# sha2017_rev1_0_0.net
KiCad netlist of a schematic drawn in EAGLE
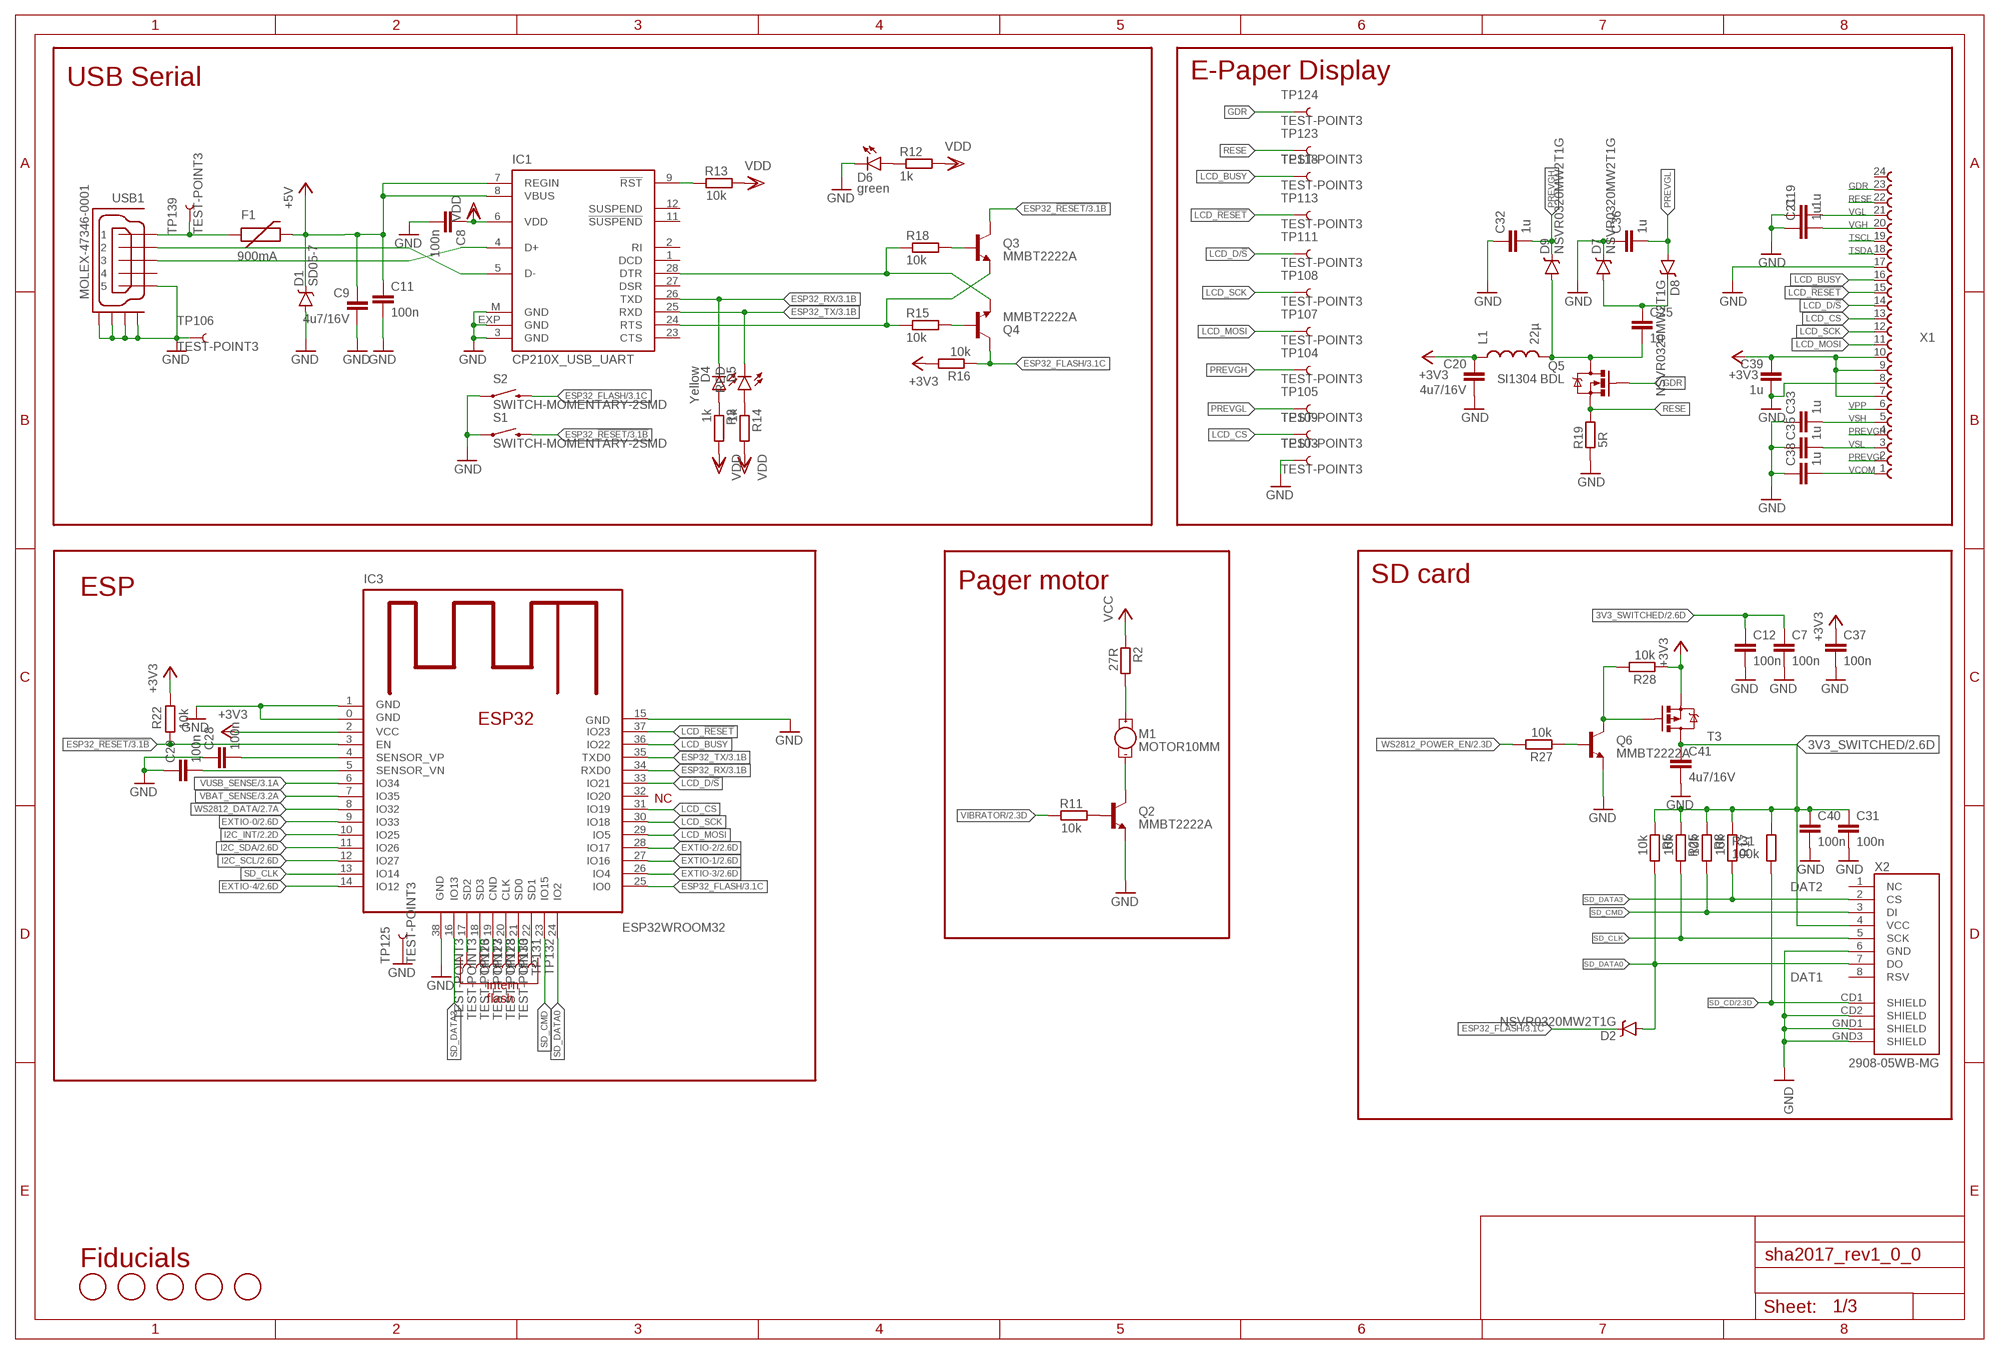
[diagram p0: schematic, sheet 1]
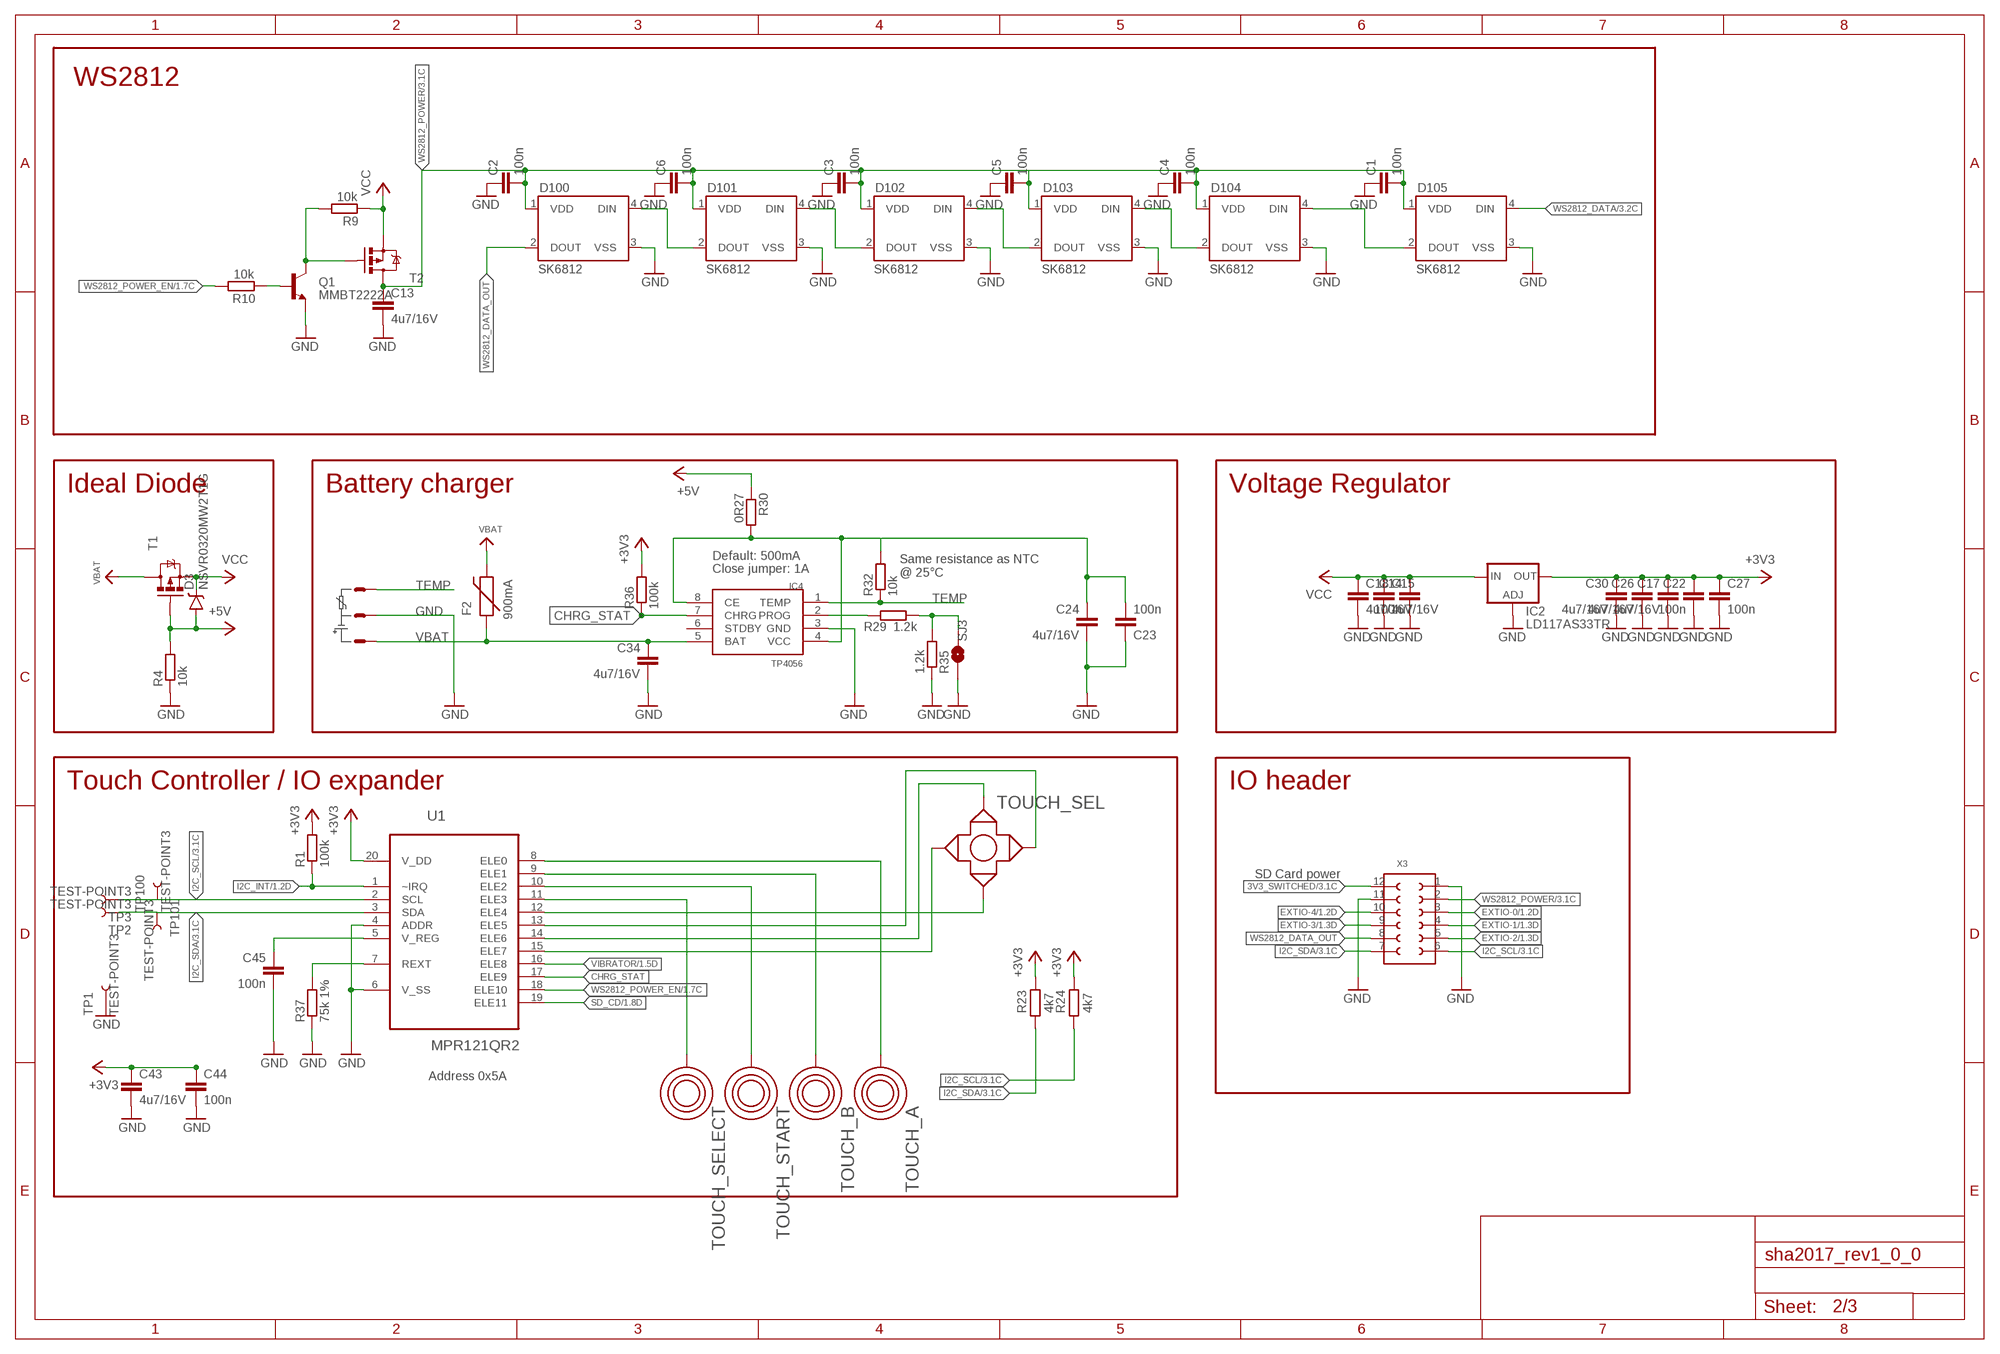
[diagram p1: schematic, sheet 2]
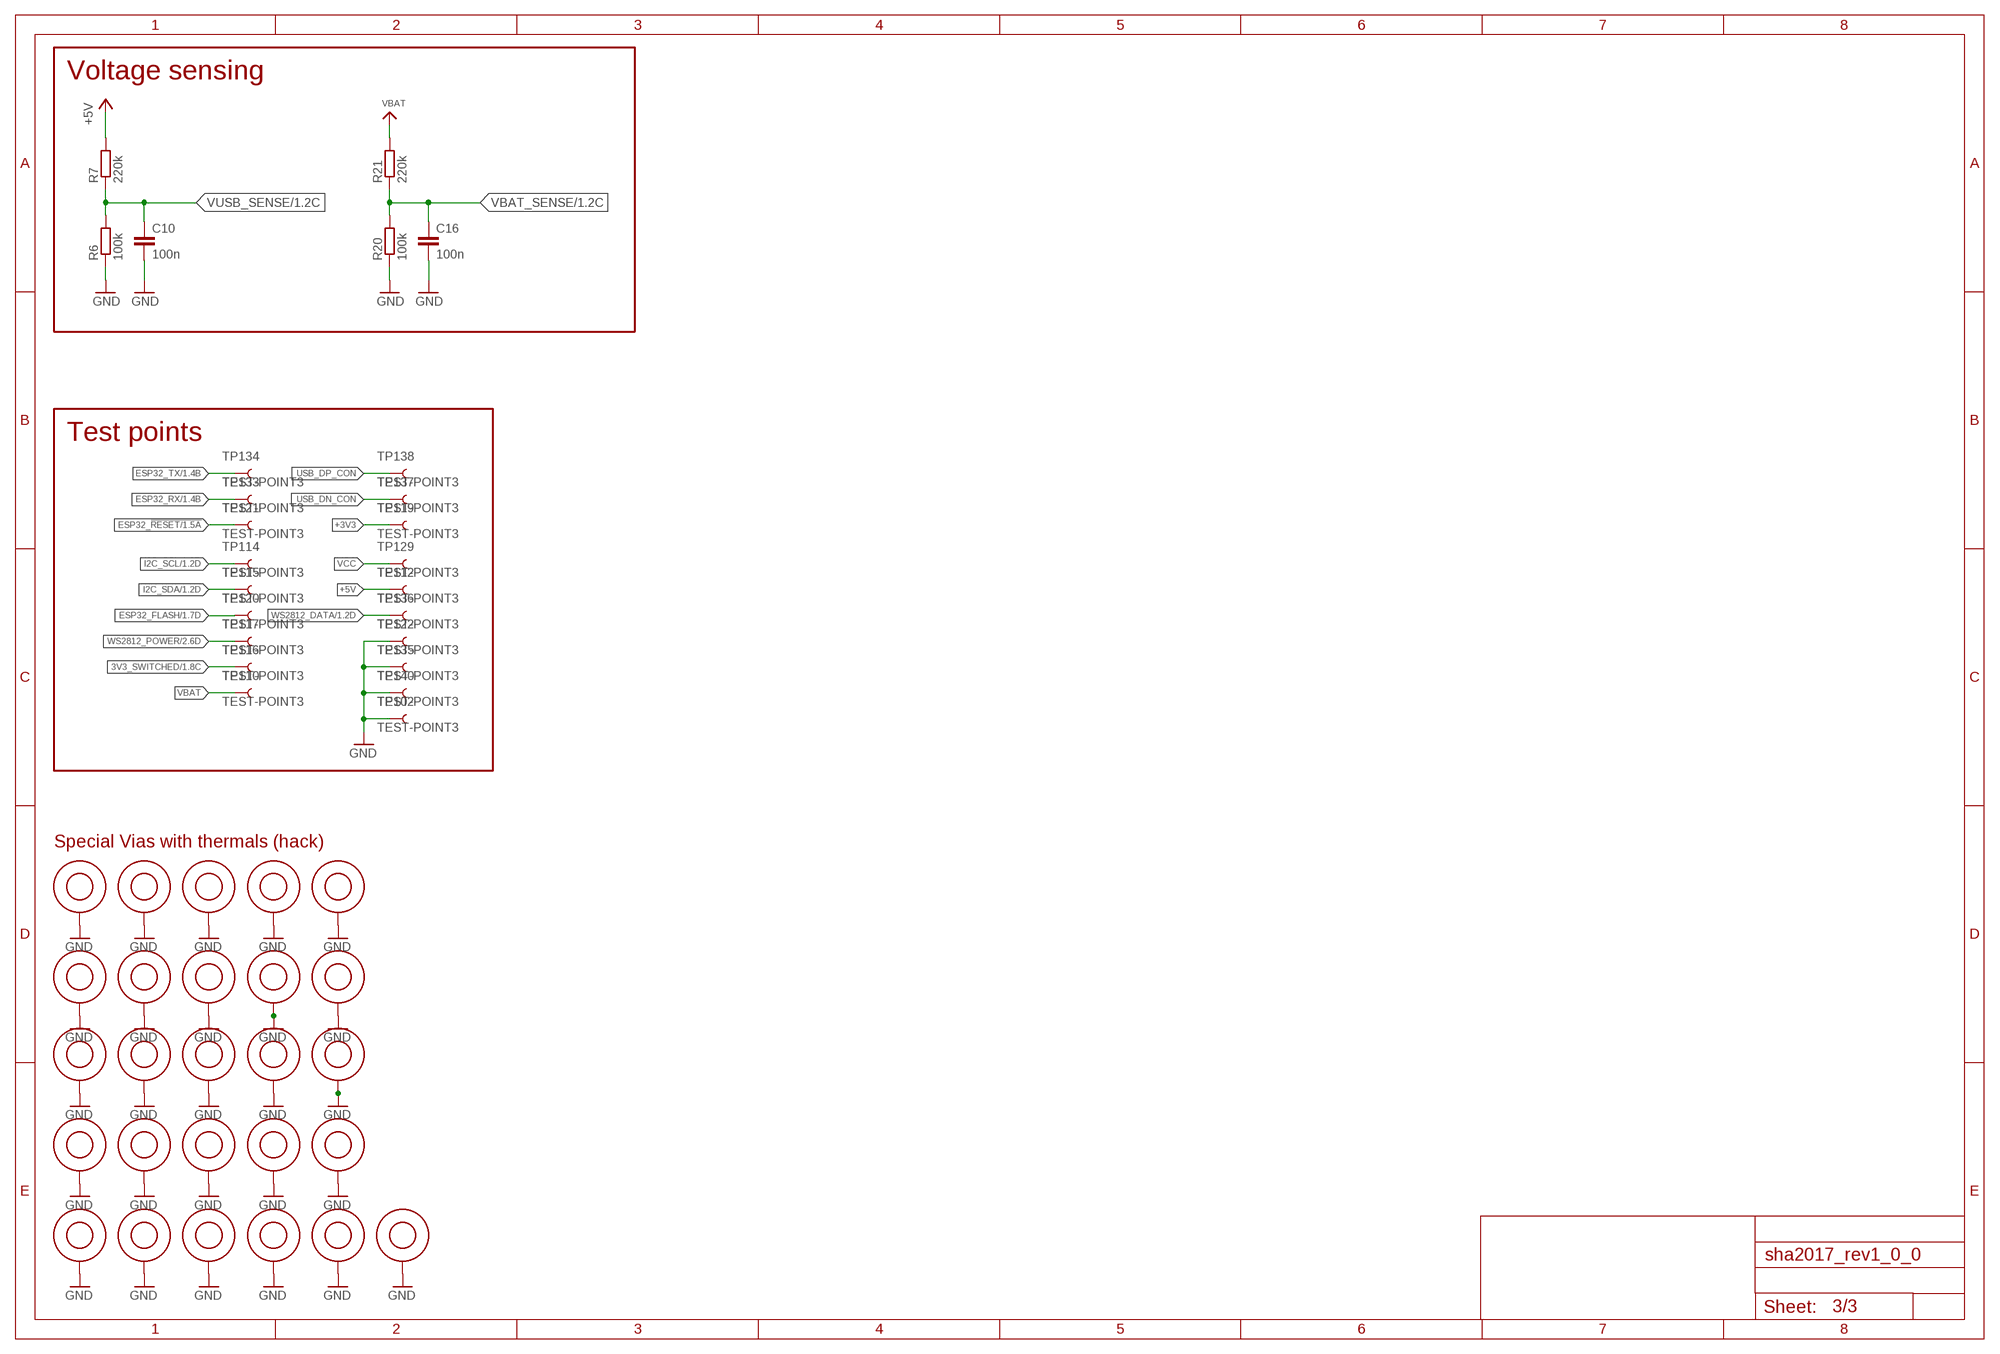
[diagram p2: schematic, sheet 3]

(export (version "E")
  (design (tool "Eeschema 10.0.6"))
  (components
    (comp (ref "$$U$1")
      (value "VIA")
      (footprint "eagle-import:VIA")
      (fields (field (name "PARTNO") "NAP"))
      (libsource (lib "eagle-import") (part "VIA"))
    )
    (comp (ref "$$U$2")
      (value "VIA")
      (footprint "eagle-import:VIA")
      (fields (field (name "PARTNO") "NAP"))
      (libsource (lib "eagle-import") (part "VIA"))
    )
    (comp (ref "$$U$3")
      (value "VIA")
      (footprint "eagle-import:VIA")
      (fields (field (name "PARTNO") "NAP"))
      (libsource (lib "eagle-import") (part "VIA"))
    )
    (comp (ref "$$U$4")
      (value "VIA")
      (footprint "eagle-import:VIA")
      (fields (field (name "PARTNO") "NAP"))
      (libsource (lib "eagle-import") (part "VIA"))
    )
    (comp (ref "$$U$5")
      (value "VIA")
      (footprint "eagle-import:VIA")
      (fields (field (name "PARTNO") "NAP"))
      (libsource (lib "eagle-import") (part "VIA"))
    )
    (comp (ref "$$U$6")
      (value "VIA")
      (footprint "eagle-import:VIA")
      (fields (field (name "PARTNO") "NAP"))
      (libsource (lib "eagle-import") (part "VIA"))
    )
    (comp (ref "$$U$7")
      (value "VIA")
      (footprint "eagle-import:VIA")
      (fields (field (name "PARTNO") "NAP"))
      (libsource (lib "eagle-import") (part "VIA"))
    )
    (comp (ref "$$U$8")
      (value "VIA")
      (footprint "eagle-import:VIA")
      (fields (field (name "PARTNO") "NAP"))
      (libsource (lib "eagle-import") (part "VIA"))
    )
    (comp (ref "$$U$9")
      (value "VIA")
      (footprint "eagle-import:VIA")
      (fields (field (name "PARTNO") "NAP"))
      (libsource (lib "eagle-import") (part "VIA"))
    )
    (comp (ref "C10")
      (value "100n")
      (footprint "eagle-import:C0603-DASHES")
      (fields (field (name "PARTNO") "GRM188R71H104KA93D"))
      (libsource (lib "eagle-import") (part "C0603-DASHES"))
    )
    (comp (ref "C16")
      (value "100n")
      (footprint "eagle-import:C0603-DASHES")
      (fields (field (name "PARTNO") "GRM188R71H104KA93D"))
      (libsource (lib "eagle-import") (part "C0603-DASHES"))
    )
    (comp (ref "R6")
      (value "100k")
      (footprint "eagle-import:R0603-DASHES")
      (fields (field (name "PARTNO") "ERJ-3GEYJ104V"))
      (libsource (lib "eagle-import") (part "sha2017_rev0_1_0_dev_R0603-DASHES"))
    )
    (comp (ref "R7")
      (value "220k")
      (footprint "eagle-import:R0603-DASHES")
      (fields (field (name "PARTNO") "ERJ-3GEYJ224V"))
      (libsource (lib "eagle-import") (part "sha2017_rev0_1_0_dev_R0603-DASHES"))
    )
    (comp (ref "R20")
      (value "100k")
      (footprint "eagle-import:R0603-DASHES")
      (fields (field (name "PARTNO") "ERJ-3GEYJ104V"))
      (libsource (lib "eagle-import") (part "sha2017_rev0_1_0_dev_R0603-DASHES"))
    )
    (comp (ref "R21")
      (value "220k")
      (footprint "eagle-import:R0603-DASHES")
      (fields (field (name "PARTNO") "ERJ-3GEYJ224V"))
      (libsource (lib "eagle-import") (part "sha2017_rev0_1_0_dev_R0603-DASHES"))
    )
    (comp (ref "TP102")
      (value "TEST-POINT3")
      (footprint "eagle-import:PAD.03X.03")
      (fields (field (name "PARTNO") "NAP"))
      (libsource (lib "eagle-import") (part "TEST-POINT3"))
    )
    (comp (ref "TP110")
      (value "TEST-POINT3")
      (footprint "eagle-import:PAD.03X.03")
      (fields (field (name "PARTNO") "NAP"))
      (libsource (lib "eagle-import") (part "TEST-POINT3"))
    )
    (comp (ref "TP112")
      (value "TEST-POINT3")
      (footprint "eagle-import:PAD.03X.03")
      (fields (field (name "PARTNO") "NAP"))
      (libsource (lib "eagle-import") (part "TEST-POINT3"))
    )
    (comp (ref "TP114")
      (value "TEST-POINT3")
      (footprint "eagle-import:PAD.03X.03")
      (fields (field (name "PARTNO") "NAP"))
      (libsource (lib "eagle-import") (part "TEST-POINT3"))
    )
    (comp (ref "TP115")
      (value "TEST-POINT3")
      (footprint "eagle-import:PAD.03X.03")
      (fields (field (name "PARTNO") "NAP"))
      (libsource (lib "eagle-import") (part "TEST-POINT3"))
    )
    (comp (ref "TP116")
      (value "TEST-POINT3")
      (footprint "eagle-import:PAD.03X.03")
      (fields (field (name "PARTNO") "NAP"))
      (libsource (lib "eagle-import") (part "TEST-POINT3"))
    )
    (comp (ref "TP117")
      (value "TEST-POINT3")
      (footprint "eagle-import:PAD.03X.03")
      (fields (field (name "PARTNO") "NAP"))
      (libsource (lib "eagle-import") (part "TEST-POINT3"))
    )
    (comp (ref "TP119")
      (value "TEST-POINT3")
      (footprint "eagle-import:PAD.03X.03")
      (fields (field (name "PARTNO") "NAP"))
      (libsource (lib "eagle-import") (part "TEST-POINT3"))
    )
    (comp (ref "TP120")
      (value "TEST-POINT3")
      (footprint "eagle-import:PAD.03X.03")
      (fields (field (name "PARTNO") "NAP"))
      (libsource (lib "eagle-import") (part "TEST-POINT3"))
    )
    (comp (ref "TP121")
      (value "TEST-POINT3")
      (footprint "eagle-import:PAD.03X.03")
      (fields (field (name "PARTNO") "NAP"))
      (libsource (lib "eagle-import") (part "TEST-POINT3"))
    )
    (comp (ref "TP122")
      (value "TEST-POINT3")
      (footprint "eagle-import:PAD.03X.03")
      (fields (field (name "PARTNO") "NAP"))
      (libsource (lib "eagle-import") (part "TEST-POINT3"))
    )
    (comp (ref "TP129")
      (value "TEST-POINT3")
      (footprint "eagle-import:PAD.03X.03")
      (fields (field (name "PARTNO") "NAP"))
      (libsource (lib "eagle-import") (part "TEST-POINT3"))
    )
    (comp (ref "TP133")
      (value "TEST-POINT3")
      (footprint "eagle-import:PAD.03X.03")
      (fields (field (name "PARTNO") "NAP"))
      (libsource (lib "eagle-import") (part "TEST-POINT3"))
    )
    (comp (ref "TP134")
      (value "TEST-POINT3")
      (footprint "eagle-import:PAD.03X.03")
      (fields (field (name "PARTNO") "NAP"))
      (libsource (lib "eagle-import") (part "TEST-POINT3"))
    )
    (comp (ref "TP135")
      (value "TEST-POINT3")
      (footprint "eagle-import:PAD.03X.03")
      (fields (field (name "PARTNO") "NAP"))
      (libsource (lib "eagle-import") (part "TEST-POINT3"))
    )
    (comp (ref "TP136")
      (value "TEST-POINT3")
      (footprint "eagle-import:PAD.03X.03")
      (fields (field (name "PARTNO") "NAP"))
      (libsource (lib "eagle-import") (part "TEST-POINT3"))
    )
    (comp (ref "TP137")
      (value "TEST-POINT3")
      (footprint "eagle-import:PAD.03X.03")
      (fields (field (name "PARTNO") "NAP"))
      (libsource (lib "eagle-import") (part "TEST-POINT3"))
    )
    (comp (ref "TP138")
      (value "TEST-POINT3")
      (footprint "eagle-import:PAD.03X.03")
      (fields (field (name "PARTNO") "NAP"))
      (libsource (lib "eagle-import") (part "TEST-POINT3"))
    )
    (comp (ref "TP140")
      (value "TEST-POINT3")
      (footprint "eagle-import:PAD.03X.03")
      (fields (field (name "PARTNO") "NAP"))
      (libsource (lib "eagle-import") (part "TEST-POINT3"))
    )
    (comp (ref "U$2")
      (value "VIA")
      (footprint "eagle-import:VIA")
      (fields (field (name "PARTNO") "NAP"))
      (libsource (lib "eagle-import") (part "VIA"))
    )
    (comp (ref "U$3")
      (value "VIA")
      (footprint "eagle-import:VIA")
      (fields (field (name "PARTNO") "NAP"))
      (libsource (lib "eagle-import") (part "VIA"))
    )
    (comp (ref "U$4")
      (value "VIA")
      (footprint "eagle-import:VIA")
      (fields (field (name "PARTNO") "NAP"))
      (libsource (lib "eagle-import") (part "VIA"))
    )
    (comp (ref "U$5")
      (value "VIA")
      (footprint "eagle-import:VIA")
      (fields (field (name "PARTNO") "NAP"))
      (libsource (lib "eagle-import") (part "VIA"))
    )
    (comp (ref "U$6")
      (value "VIA")
      (footprint "eagle-import:VIA")
      (fields (field (name "PARTNO") "NAP"))
      (libsource (lib "eagle-import") (part "VIA"))
    )
    (comp (ref "U$10")
      (value "VIA")
      (footprint "eagle-import:VIA")
      (fields (field (name "PARTNO") "NAP"))
      (libsource (lib "eagle-import") (part "VIA"))
    )
    (comp (ref "U$11")
      (value "VIA")
      (footprint "eagle-import:VIA")
      (fields (field (name "PARTNO") "NAP"))
      (libsource (lib "eagle-import") (part "VIA"))
    )
    (comp (ref "U$12")
      (value "VIA")
      (footprint "eagle-import:VIA")
      (fields (field (name "PARTNO") "NAP"))
      (libsource (lib "eagle-import") (part "VIA"))
    )
    (comp (ref "U$13")
      (value "VIA")
      (footprint "eagle-import:VIA")
      (fields (field (name "PARTNO") "NAP"))
      (libsource (lib "eagle-import") (part "VIA"))
    )
    (comp (ref "U$14")
      (value "VIA")
      (footprint "eagle-import:VIA")
      (fields (field (name "PARTNO") "NAP"))
      (libsource (lib "eagle-import") (part "VIA"))
    )
    (comp (ref "U$15")
      (value "VIA")
      (footprint "eagle-import:VIA")
      (fields (field (name "PARTNO") "NAP"))
      (libsource (lib "eagle-import") (part "VIA"))
    )
    (comp (ref "U$16")
      (value "VIA")
      (footprint "eagle-import:VIA")
      (fields (field (name "PARTNO") "NAP"))
      (libsource (lib "eagle-import") (part "VIA"))
    )
    (comp (ref "U$17")
      (value "VIA")
      (footprint "eagle-import:VIA")
      (fields (field (name "PARTNO") "NAP"))
      (libsource (lib "eagle-import") (part "VIA"))
    )
    (comp (ref "U$18")
      (value "VIA")
      (footprint "eagle-import:VIA")
      (fields (field (name "PARTNO") "NAP"))
      (libsource (lib "eagle-import") (part "VIA"))
    )
    (comp (ref "U$19")
      (value "VIA")
      (footprint "eagle-import:VIA")
      (fields (field (name "PARTNO") "NAP"))
      (libsource (lib "eagle-import") (part "VIA"))
    )
    (comp (ref "U$20")
      (value "VIA")
      (footprint "eagle-import:VIA")
      (fields (field (name "PARTNO") "NAP"))
      (libsource (lib "eagle-import") (part "VIA"))
    )
    (comp (ref "U$21")
      (value "VIA")
      (footprint "eagle-import:VIA")
      (fields (field (name "PARTNO") "NAP"))
      (libsource (lib "eagle-import") (part "VIA"))
    )
    (comp (ref "U$22")
      (value "VIA")
      (footprint "eagle-import:VIA")
      (fields (field (name "PARTNO") "NAP"))
      (libsource (lib "eagle-import") (part "VIA"))
    )
    (comp (ref "U$23")
      (value "VIA")
      (footprint "eagle-import:VIA")
      (fields (field (name "PARTNO") "NAP"))
      (libsource (lib "eagle-import") (part "VIA"))
    )
    (comp (ref "C1")
      (value "100n")
      (footprint "eagle-import:C0603-DASHES")
      (fields (field (name "PARTNO") "GRM188R71H104KA93D"))
      (libsource (lib "eagle-import") (part "C0603-DASHES"))
    )
    (comp (ref "C2")
      (value "100n")
      (footprint "eagle-import:C0603-DASHES")
      (fields (field (name "PARTNO") "GRM188R71H104KA93D"))
      (libsource (lib "eagle-import") (part "C0603-DASHES"))
    )
    (comp (ref "C3")
      (value "100n")
      (footprint "eagle-import:C0603-DASHES")
      (fields (field (name "PARTNO") "GRM188R71H104KA93D"))
      (libsource (lib "eagle-import") (part "C0603-DASHES"))
    )
    (comp (ref "C4")
      (value "100n")
      (footprint "eagle-import:C0603-DASHES")
      (fields (field (name "PARTNO") "GRM188R71H104KA93D"))
      (libsource (lib "eagle-import") (part "C0603-DASHES"))
    )
    (comp (ref "C5")
      (value "100n")
      (footprint "eagle-import:C0603-DASHES")
      (fields (field (name "PARTNO") "GRM188R71H104KA93D"))
      (libsource (lib "eagle-import") (part "C0603-DASHES"))
    )
    (comp (ref "C6")
      (value "100n")
      (footprint "eagle-import:C0603-DASHES")
      (fields (field (name "PARTNO") "GRM188R71H104KA93D"))
      (libsource (lib "eagle-import") (part "C0603-DASHES"))
    )
    (comp (ref "C13")
      (value "4u7/16V")
      (footprint "eagle-import:C0805")
      (fields (field (name "PARTNO") "GRM21BR61C475KA88K"))
      (libsource (lib "eagle-import") (part "C-EUC0805"))
    )
    (comp (ref "C14")
      (value "100n")
      (footprint "eagle-import:C0603-DASHES")
      (fields (field (name "PARTNO") "GRM188R71H104KA93D"))
      (libsource (lib "eagle-import") (part "C0603-DASHES"))
    )
    (comp (ref "C15")
      (value "4u7/16V")
      (footprint "eagle-import:C0805")
      (fields (field (name "PARTNO") "GRM21BR61C475KA88K"))
      (libsource (lib "eagle-import") (part "C-EUC0805"))
    )
    (comp (ref "C17")
      (value "4u7/16V")
      (footprint "eagle-import:C0805")
      (fields (field (name "PARTNO") "GRM21BR61C475KA88K"))
      (libsource (lib "eagle-import") (part "C-EUC0805"))
    )
    (comp (ref "C18")
      (value "4u7/16V")
      (footprint "eagle-import:C0805")
      (fields (field (name "PARTNO") "GRM21BR61C475KA88K"))
      (libsource (lib "eagle-import") (part "C-EUC0805"))
    )
    (comp (ref "C22")
      (value "100n")
      (footprint "eagle-import:C0603-DASHES")
      (fields (field (name "PARTNO") "GRM188R71H104KA93D"))
      (libsource (lib "eagle-import") (part "C0603-DASHES"))
    )
    (comp (ref "C23")
      (value "100n")
      (footprint "eagle-import:C0603-DASHES")
      (fields (field (name "PARTNO") "GRM188R71H104KA93D"))
      (libsource (lib "eagle-import") (part "C0603-DASHES"))
    )
    (comp (ref "C24")
      (value "4u7/16V")
      (footprint "eagle-import:C0805")
      (fields (field (name "PARTNO") "GRM21BR61C475KA88K"))
      (libsource (lib "eagle-import") (part "C-EUC0805"))
    )
    (comp (ref "C26")
      (value "4u7/16V")
      (footprint "eagle-import:C0805")
      (fields (field (name "PARTNO") "GRM21BR61C475KA88K"))
      (libsource (lib "eagle-import") (part "C-EUC0805"))
    )
    (comp (ref "C27")
      (value "100n")
      (footprint "eagle-import:C0603-DASHES")
      (fields (field (name "PARTNO") "GRM188R71H104KA93D"))
      (libsource (lib "eagle-import") (part "C0603-DASHES"))
    )
    (comp (ref "C30")
      (value "4u7/16V")
      (footprint "eagle-import:C0805")
      (fields (field (name "PARTNO") "GRM21BR61C475KA88K"))
      (libsource (lib "eagle-import") (part "C-EUC0805"))
    )
    (comp (ref "C34")
      (value "4u7/16V")
      (footprint "eagle-import:C0805")
      (fields (field (name "PARTNO") "GRM21BR61C475KA88K"))
      (libsource (lib "eagle-import") (part "C-EUC0805"))
    )
    (comp (ref "C43")
      (value "4u7/16V")
      (footprint "eagle-import:C0805")
      (fields (field (name "PARTNO") "GRM21BR61C475KA88K"))
      (libsource (lib "eagle-import") (part "C-EUC0805"))
    )
    (comp (ref "C44")
      (value "100n")
      (footprint "eagle-import:C0603-DASHES")
      (fields (field (name "PARTNO") "GRM188R71H104KA93D"))
      (libsource (lib "eagle-import") (part "C0603-DASHES"))
    )
    (comp (ref "C45")
      (value "100n")
      (footprint "eagle-import:C0603-DASHES")
      (fields (field (name "PARTNO") "GRM188R71H104KA93D"))
      (libsource (lib "eagle-import") (part "C0603-DASHES"))
    )
    (comp (ref "D3")
      (value "NSVR0320MW2T1G")
      (footprint "eagle-import:SOD-323")
      (fields (field (name "PARTNO") "BAT20JFILM"))
      (libsource (lib "eagle-import") (part "BAT20JFILM"))
    )
    (comp (ref "D100")
      (value "SK6812")
      (footprint "eagle-import:WS2812B")
      (libsource (lib "eagle-import") (part "WS2812B"))
    )
    (comp (ref "D101")
      (value "SK6812")
      (footprint "eagle-import:WS2812B")
      (libsource (lib "eagle-import") (part "WS2812B"))
    )
    (comp (ref "D102")
      (value "SK6812")
      (footprint "eagle-import:WS2812B")
      (libsource (lib "eagle-import") (part "WS2812B"))
    )
    (comp (ref "D103")
      (value "SK6812")
      (footprint "eagle-import:WS2812B")
      (libsource (lib "eagle-import") (part "WS2812B"))
    )
    (comp (ref "D104")
      (value "SK6812")
      (footprint "eagle-import:WS2812B")
      (libsource (lib "eagle-import") (part "WS2812B"))
    )
    (comp (ref "D105")
      (value "SK6812")
      (footprint "eagle-import:WS2812B")
      (libsource (lib "eagle-import") (part "WS2812B"))
    )
    (comp (ref "F2")
      (value "900mA")
      (footprint "eagle-import:PTC-1206")
      (libsource (lib "eagle-import") (part "PTCSMD"))
    )
    (comp (ref "IC2")
      (value "LD117AS33TR")
      (footprint "eagle-import:SOT223")
      (fields (field (name "PARTNO") "AP7215-33YG-13"))
      (libsource (lib "eagle-import") (part "LD117A?S33TR"))
    )
    (comp (ref "IC4")
      (value "TP4056")
      (footprint "eagle-import:SOP-8")
      (libsource (lib "eagle-import") (part "TP4056"))
    )
    (comp (ref "Q1")
      (value "MMBT2222A")
      (footprint "eagle-import:SOT23-3")
      (fields (field (name "PARTNO") "BC817-25,215"))
      (libsource (lib "eagle-import") (part "TRANSISTOR_NPNMMBT2222A"))
    )
    (comp (ref "R1")
      (value "100k")
      (footprint "eagle-import:R0603-DASHES")
      (fields (field (name "PARTNO") "ERJ-3GEYJ104V"))
      (libsource (lib "eagle-import") (part "sha2017_rev0_1_0_dev_R0603-DASHES"))
    )
    (comp (ref "R4")
      (value "10k")
      (footprint "eagle-import:R0603-DASHES")
      (fields (field (name "PARTNO") "ERJ-3GEYJ103V"))
      (libsource (lib "eagle-import") (part "sha2017_rev0_1_0_dev_R0603-DASHES"))
    )
    (comp (ref "R9")
      (value "10k")
      (footprint "eagle-import:R0603-DASHES")
      (fields (field (name "PARTNO") "ERJ-3GEYJ103V"))
      (libsource (lib "eagle-import") (part "R0603-DASHES"))
    )
    (comp (ref "R10")
      (value "10k")
      (footprint "eagle-import:R0603-DASHES")
      (fields (field (name "PARTNO") "ERJ-3GEYJ103V"))
      (libsource (lib "eagle-import") (part "R0603-DASHES"))
    )
    (comp (ref "R23")
      (value "4k7")
      (footprint "eagle-import:R0603-DASHES")
      (fields (field (name "PARTNO") "ERJ-3GEYJ103V"))
      (libsource (lib "eagle-import") (part "sha2017_rev0_1_0_dev_R0603-DASHES"))
    )
    (comp (ref "R24")
      (value "4k7")
      (footprint "eagle-import:R0603-DASHES")
      (fields (field (name "PARTNO") "ERJ-3GEYJ103V"))
      (libsource (lib "eagle-import") (part "sha2017_rev0_1_0_dev_R0603-DASHES"))
    )
    (comp (ref "R29")
      (value "1.2k")
      (footprint "eagle-import:R0603-DASHES")
      (fields (field (name "PARTNO") "ERJ-3GEYJ222V"))
      (libsource (lib "eagle-import") (part "sha2017_rev0_1_0_dev_R0603-DASHES"))
    )
    (comp (ref "R30")
      (value "0R27")
      (footprint "eagle-import:R1206")
      (fields (field (name "PARTNO") "ERJ-3GEYJ154V"))
      (libsource (lib "eagle-import") (part "R-EU_R1206"))
    )
    (comp (ref "R32")
      (value "10k")
      (footprint "eagle-import:R0603-DASHES")
      (fields (field (name "PARTNO") "ERJ-3GEYJ154V"))
      (libsource (lib "eagle-import") (part "sha2017_rev0_1_0_dev_R0603-DASHES"))
    )
    (comp (ref "R35")
      (value "1.2k")
      (footprint "eagle-import:R0603-DASHES")
      (fields (field (name "PARTNO") "ERJ-3GEYJ222V"))
      (libsource (lib "eagle-import") (part "sha2017_rev0_1_0_dev_R0603-DASHES"))
    )
    (comp (ref "R36")
      (value "100k")
      (footprint "eagle-import:R0603-DASHES")
      (fields (field (name "PARTNO") "ERJ-3GEYJ104V"))
      (libsource (lib "eagle-import") (part "sha2017_rev0_1_0_dev_R0603-DASHES"))
    )
    (comp (ref "R37")
      (value "75k 1%")
      (footprint "eagle-import:R0603-DASHES")
      (fields (field (name "PARTNO") "ERJ-3GEYJ104V"))
      (libsource (lib "eagle-import") (part "sha2017_rev0_1_0_dev_R0603-DASHES"))
    )
    (comp (ref "SJ3")
      (value "JUMPER-PAD-2-NOYES_SILK")
      (footprint "eagle-import:PAD-JUMPER-2-NO_YES_SILK")
      (fields (field (name "PARTNO") "NAP"))
      (libsource (lib "eagle-import") (part "JUMPER-PAD-2-NOYES_SILK"))
    )
    (comp (ref "T1")
      (value "MOSFET-PCHANNEL")
      (footprint "eagle-import:SOT23-3")
      (libsource (lib "eagle-import") (part "MOSFET-PCHANNEL"))
    )
    (comp (ref "T2")
      (value "MOSFET-PCHANNEL")
      (footprint "eagle-import:SOT23-3")
      (libsource (lib "eagle-import") (part "MOSFET-PCHANNEL"))
    )
    (comp (ref "TOUCH_A")
      (value "TOUCHROUND")
      (footprint "eagle-import:TOUCH_BUTTON")
      (fields (field (name "PARTNO") "NAP"))
      (libsource (lib "eagle-import") (part "TOUCHROUND"))
    )
    (comp (ref "TOUCH_B")
      (value "TOUCHROUND")
      (footprint "eagle-import:TOUCH_BUTTON")
      (fields (field (name "PARTNO") "NAP"))
      (libsource (lib "eagle-import") (part "TOUCHROUND"))
    )
    (comp (ref "TOUCH_SEL")
      (value "TOUCH_CROSS")
      (footprint "eagle-import:TOUCH_CROSS")
      (fields (field (name "PARTNO") "NAP"))
      (libsource (lib "eagle-import") (part "TOUCH_CROSS"))
    )
    (comp (ref "TOUCH_SELECT")
      (value "TOUCHSELECT")
      (footprint "eagle-import:TOUCH_SELECT")
      (libsource (lib "eagle-import") (part "TOUCHSELECT"))
    )
    (comp (ref "TOUCH_START")
      (value "TOUCHSELECT")
      (footprint "eagle-import:TOUCH_SELECT")
      (libsource (lib "eagle-import") (part "TOUCHSELECT"))
    )
    (comp (ref "TP1")
      (value "TEST-POINT3")
      (footprint "eagle-import:PAD.03X.03")
      (fields (field (name "PARTNO") "NAP"))
      (libsource (lib "eagle-import") (part "TEST-POINT3"))
    )
    (comp (ref "TP2")
      (value "TEST-POINT3")
      (footprint "eagle-import:PAD.03X.03")
      (fields (field (name "PARTNO") "NAP"))
      (libsource (lib "eagle-import") (part "TEST-POINT3"))
    )
    (comp (ref "TP3")
      (value "TEST-POINT3")
      (footprint "eagle-import:PAD.03X.03")
      (fields (field (name "PARTNO") "NAP"))
      (libsource (lib "eagle-import") (part "TEST-POINT3"))
    )
    (comp (ref "TP100")
      (value "TEST-POINT3")
      (footprint "eagle-import:PAD.03X.03")
      (fields (field (name "PARTNO") "NAP"))
      (libsource (lib "eagle-import") (part "TEST-POINT3"))
    )
    (comp (ref "TP101")
      (value "TEST-POINT3")
      (footprint "eagle-import:PAD.03X.03")
      (fields (field (name "PARTNO") "NAP"))
      (libsource (lib "eagle-import") (part "TEST-POINT3"))
    )
    (comp (ref "U1")
      (value "MPR121QR2")
      (footprint "eagle-import:QFN40P300X300X60-20N")
      (libsource (lib "eagle-import") (part "MPR121QR2"))
    )
    (comp (ref "X3")
      (value "610X12243021")
      (footprint "eagle-import:610X12243021")
      (fields (field (name "PARTNO") "517-153208-2020-TB"))
      (libsource (lib "eagle-import") (part "610X12243021"))
    )
    (comp (ref "X4")
      (value "JST-PH3")
      (footprint "eagle-import:JST-PH3")
      (libsource (lib "eagle-import") (part "JST-PH3"))
    )
    (comp (ref "C7")
      (value "100n")
      (footprint "eagle-import:C0603-DASHES")
      (fields (field (name "PARTNO") "GRM188R71H104KA93D"))
      (libsource (lib "eagle-import") (part "C0603-DASHES"))
    )
    (comp (ref "C8")
      (value "100n")
      (footprint "eagle-import:C0603-DASHES")
      (fields (field (name "PARTNO") "GRM188R71H104KA93D"))
      (libsource (lib "eagle-import") (part "C0603-DASHES"))
    )
    (comp (ref "C9")
      (value "4u7/16V")
      (footprint "eagle-import:C0805")
      (fields (field (name "PARTNO") "GRM21BR61C475KA88K"))
      (libsource (lib "eagle-import") (part "C-EUC0805"))
    )
    (comp (ref "C11")
      (value "100n")
      (footprint "eagle-import:C0603-DASHES")
      (fields (field (name "PARTNO") "GRM188R71H104KA93D"))
      (libsource (lib "eagle-import") (part "C0603-DASHES"))
    )
    (comp (ref "C12")
      (value "100n")
      (footprint "eagle-import:C0603-DASHES")
      (fields (field (name "PARTNO") "GRM188R71H104KA93D"))
      (libsource (lib "eagle-import") (part "C0603-DASHES"))
    )
    (comp (ref "C19")
      (value "1u")
      (footprint "eagle-import:C0603-DASHES")
      (fields (field (name "PARTNO") "GRM188R61E105KA12D"))
      (libsource (lib "eagle-import") (part "C0603-DASHES"))
    )
    (comp (ref "C20")
      (value "4u7/16V")
      (footprint "eagle-import:C0805")
      (fields (field (name "PARTNO") "GRM21BR61C475KA88K"))
      (libsource (lib "eagle-import") (part "C-EUC0805"))
    )
    (comp (ref "C21")
      (value "1u")
      (footprint "eagle-import:C0603-DASHES")
      (fields (field (name "PARTNO") "GRM188R61E105KA12D"))
      (libsource (lib "eagle-import") (part "C0603-DASHES"))
    )
    (comp (ref "C25")
      (value "1u")
      (footprint "eagle-import:C0603-DASHES")
      (fields (field (name "PARTNO") "GRM188R61E105KA12D"))
      (libsource (lib "eagle-import") (part "C0603-DASHES"))
    )
    (comp (ref "C28")
      (value "100n")
      (footprint "eagle-import:C0603-DASHES")
      (fields (field (name "PARTNO") "GRM188R71H104KA93D"))
      (libsource (lib "eagle-import") (part "C0603-DASHES"))
    )
    (comp (ref "C29")
      (value "100n")
      (footprint "eagle-import:C0603-DASHES")
      (fields (field (name "PARTNO") "GRM188R71H104KA93D"))
      (libsource (lib "eagle-import") (part "C0603-DASHES"))
    )
    (comp (ref "C31")
      (value "100n")
      (footprint "eagle-import:C0603-DASHES")
      (fields (field (name "PARTNO") "GRM188R71H104KA93D"))
      (libsource (lib "eagle-import") (part "C0603-DASHES"))
    )
    (comp (ref "C32")
      (value "1u")
      (footprint "eagle-import:C0603-DASHES")
      (fields (field (name "PARTNO") "GRM188R61E105KA12D"))
      (libsource (lib "eagle-import") (part "C0603-DASHES"))
    )
    (comp (ref "C33")
      (value "1u")
      (footprint "eagle-import:C0603-DASHES")
      (fields (field (name "PARTNO") "GRM188R61E105KA12D"))
      (libsource (lib "eagle-import") (part "C0603-DASHES"))
    )
    (comp (ref "C35")
      (value "1u")
      (footprint "eagle-import:C0603-DASHES")
      (fields (field (name "PARTNO") "GRM188R61E105KA12D"))
      (libsource (lib "eagle-import") (part "C0603-DASHES"))
    )
    (comp (ref "C36")
      (value "1u")
      (footprint "eagle-import:C0603-DASHES")
      (fields (field (name "PARTNO") "GRM188R61E105KA12D"))
      (libsource (lib "eagle-import") (part "C0603-DASHES"))
    )
    (comp (ref "C37")
      (value "100n")
      (footprint "eagle-import:C0603-DASHES")
      (fields (field (name "PARTNO") "GRM188R71H104KA93D"))
      (libsource (lib "eagle-import") (part "C0603-DASHES"))
    )
    (comp (ref "C38")
      (value "1u")
      (footprint "eagle-import:C0603-DASHES")
      (fields (field (name "PARTNO") "GRM188R61E105KA12D"))
      (libsource (lib "eagle-import") (part "C0603-DASHES"))
    )
    (comp (ref "C39")
      (value "1u")
      (footprint "eagle-import:C0603-DASHES")
      (fields (field (name "PARTNO") "GRM188R61E105KA12D"))
      (libsource (lib "eagle-import") (part "C0603-DASHES"))
    )
    (comp (ref "C40")
      (value "100n")
      (footprint "eagle-import:C0603-DASHES")
      (fields (field (name "PARTNO") "GRM188R71H104KA93D"))
      (libsource (lib "eagle-import") (part "C0603-DASHES"))
    )
    (comp (ref "C41")
      (value "4u7/16V")
      (footprint "eagle-import:C0805")
      (fields (field (name "PARTNO") "GRM21BR61C475KA88K"))
      (libsource (lib "eagle-import") (part "C-EUC0805"))
    )
    (comp (ref "D1")
      (value "SD05-7")
      (footprint "eagle-import:SOD-323")
      (libsource (lib "eagle-import") (part "DIODE-SCHOTTKY-PMEG4005EJ"))
    )
    (comp (ref "D2")
      (value "NSVR0320MW2T1G")
      (footprint "eagle-import:SOD-323")
      (fields (field (name "PARTNO") "BAT20JFILM"))
      (libsource (lib "eagle-import") (part "BAT20JFILM"))
    )
    (comp (ref "D4")
      (value "Yellow")
      (footprint "eagle-import:LED-0603")
      (libsource (lib "eagle-import") (part "LED0603"))
    )
    (comp (ref "D5")
      (value "RED")
      (footprint "eagle-import:LED-0603")
      (libsource (lib "eagle-import") (part "LED0603"))
    )
    (comp (ref "D6")
      (value "green")
      (footprint "eagle-import:LED-0603")
      (libsource (lib "eagle-import") (part "LED0603"))
    )
    (comp (ref "D7")
      (value "NSVR0320MW2T1G")
      (footprint "eagle-import:SOD-323")
      (fields (field (name "PARTNO") "BAT20JFILM"))
      (libsource (lib "eagle-import") (part "BAT20JFILM"))
    )
    (comp (ref "D8")
      (value "NSVR0320MW2T1G")
      (footprint "eagle-import:SOD-323")
      (fields (field (name "PARTNO") "BAT20JFILM"))
      (libsource (lib "eagle-import") (part "BAT20JFILM"))
    )
    (comp (ref "D9")
      (value "NSVR0320MW2T1G")
      (footprint "eagle-import:SOD-323")
      (fields (field (name "PARTNO") "BAT20JFILM"))
      (libsource (lib "eagle-import") (part "BAT20JFILM"))
    )
    (comp (ref "F1")
      (value "900mA")
      (footprint "eagle-import:PTC-1206")
      (libsource (lib "eagle-import") (part "PTCSMD"))
    )
    (comp (ref "FD1")
      (value "FIDUCIAL")
      (footprint "eagle-import:FIDUCIAL_1MM")
      (fields (field (name "PARTNO") "NAP"))
      (libsource (lib "eagle-import") (part "FIDUCIAL"))
    )
    (comp (ref "FD2")
      (value "FIDUCIAL")
      (footprint "eagle-import:FIDUCIAL_1MM")
      (fields (field (name "PARTNO") "NAP"))
      (libsource (lib "eagle-import") (part "FIDUCIAL"))
    )
    (comp (ref "FD3")
      (value "FIDUCIAL")
      (footprint "eagle-import:FIDUCIAL_1MM")
      (fields (field (name "PARTNO") "NAP"))
      (libsource (lib "eagle-import") (part "FIDUCIAL"))
    )
    (comp (ref "FD4")
      (value "FIDUCIAL")
      (footprint "eagle-import:FIDUCIAL_1MM")
      (fields (field (name "PARTNO") "NAP"))
      (libsource (lib "eagle-import") (part "FIDUCIAL"))
    )
    (comp (ref "FD5")
      (value "FIDUCIAL")
      (footprint "eagle-import:FIDUCIAL_1MM")
      (fields (field (name "PARTNO") "NAP"))
      (libsource (lib "eagle-import") (part "FIDUCIAL"))
    )
    (comp (ref "IC1")
      (value "CP210X_USB_UART")
      (footprint "eagle-import:MLP28")
      (fields (field (name "PARTNO") "CP2102-GMR"))
      (libsource (lib "eagle-import") (part "CP210X_USB_UART"))
    )
    (comp (ref "IC3")
      (value "ESP32WROOM32")
      (footprint "eagle-import:ESP32MOD")
      (libsource (lib "eagle-import") (part "ESP32WROOM32"))
    )
    (comp (ref "L1")
      (value "22µ")
      (footprint "eagle-import:1210")
      (fields (field (name "PARTNO") "NLCV32T-220K-EF"))
      (libsource (lib "eagle-import") (part "INDUCTOR1210"))
    )
    (comp (ref "M1")
      (value "MOTOR10MM")
      (footprint "eagle-import:VIBE-MOTOR-10MM")
      (libsource (lib "eagle-import") (part "MOTOR10MM"))
    )
    (comp (ref "Q2")
      (value "MMBT2222A")
      (footprint "eagle-import:SOT23-3")
      (fields (field (name "PARTNO") "BC817-25,215"))
      (libsource (lib "eagle-import") (part "TRANSISTOR_NPNMMBT2222A"))
    )
    (comp (ref "Q3")
      (value "MMBT2222A")
      (footprint "eagle-import:SOT23-3")
      (fields (field (name "PARTNO") "BC817-25,215"))
      (libsource (lib "eagle-import") (part "TRANSISTOR_NPNMMBT2222A"))
    )
    (comp (ref "Q4")
      (value "MMBT2222A")
      (footprint "eagle-import:SOT23-3")
      (fields (field (name "PARTNO") "BC817-25,215"))
      (libsource (lib "eagle-import") (part "TRANSISTOR_NPNMMBT2222A"))
    )
    (comp (ref "Q5")
      (value "SI1304 BDL")
      (footprint "eagle-import:SOT323")
      (fields (field (name "PARTNO") "SI1308EDL-T1-GE3"))
      (libsource (lib "eagle-import") (part "MOSFET-NCHANNEL2N7002PW"))
    )
    (comp (ref "Q6")
      (value "MMBT2222A")
      (footprint "eagle-import:SOT23-3")
      (fields (field (name "PARTNO") "BC817-25,215"))
      (libsource (lib "eagle-import") (part "TRANSISTOR_NPNMMBT2222A"))
    )
    (comp (ref "R2")
      (value "27R")
      (footprint "eagle-import:R1206")
      (fields (field (name "PARTNO") "ERJ-3GEYJ220V"))
      (libsource (lib "eagle-import") (part "R-EU_R1206"))
    )
    (comp (ref "R3")
      (value "1k")
      (footprint "eagle-import:R0603-DASHES")
      (fields (field (name "PARTNO") "ERJ-3GEYJ102V"))
      (libsource (lib "eagle-import") (part "sha2017_rev0_1_0_dev_R0603-DASHES"))
    )
    (comp (ref "R5")
      (value "10k")
      (footprint "eagle-import:R0603-DASHES")
      (fields (field (name "PARTNO") "ERJ-3GEYJ103V"))
      (libsource (lib "eagle-import") (part "R0603-DASHES"))
    )
    (comp (ref "R8")
      (value "10k")
      (footprint "eagle-import:R0603-DASHES")
      (fields (field (name "PARTNO") "ERJ-3GEYJ103V"))
      (libsource (lib "eagle-import") (part "R0603-DASHES"))
    )
    (comp (ref "R11")
      (value "10k")
      (footprint "eagle-import:R0603-DASHES")
      (fields (field (name "PARTNO") "ERJ-3GEYJ103V"))
      (libsource (lib "eagle-import") (part "R0603-DASHES"))
    )
    (comp (ref "R12")
      (value "1k")
      (footprint "eagle-import:R0603-DASHES")
      (fields (field (name "PARTNO") "ERJ-3GEYJ102V"))
      (libsource (lib "eagle-import") (part "sha2017_rev0_1_0_dev_R0603-DASHES"))
    )
    (comp (ref "R13")
      (value "10k")
      (footprint "eagle-import:R0603-DASHES")
      (fields (field (name "PARTNO") "ERJ-3GEYJ103V"))
      (libsource (lib "eagle-import") (part "sha2017_rev0_1_0_dev_R0603-DASHES"))
    )
    (comp (ref "R14")
      (value "1k")
      (footprint "eagle-import:R0603-DASHES")
      (fields (field (name "PARTNO") "ERJ-3GEYJ102V"))
      (libsource (lib "eagle-import") (part "sha2017_rev0_1_0_dev_R0603-DASHES"))
    )
    (comp (ref "R15")
      (value "10k")
      (footprint "eagle-import:R0603-DASHES")
      (fields (field (name "PARTNO") "ERJ-3GEYJ103V"))
      (libsource (lib "eagle-import") (part "sha2017_rev0_1_0_dev_R0603-DASHES"))
    )
    (comp (ref "R16")
      (value "10k")
      (footprint "eagle-import:R0603-DASHES")
      (fields (field (name "PARTNO") "ERJ-3GEYJ103V"))
      (libsource (lib "eagle-import") (part "sha2017_rev0_1_0_dev_R0603-DASHES"))
    )
    (comp (ref "R17")
      (value "10k")
      (footprint "eagle-import:R0603-DASHES")
      (fields (field (name "PARTNO") "ERJ-3GEYJ103V"))
      (libsource (lib "eagle-import") (part "sha2017_rev0_1_0_dev_R0603-DASHES"))
    )
    (comp (ref "R18")
      (value "10k")
      (footprint "eagle-import:R0603-DASHES")
      (fields (field (name "PARTNO") "ERJ-3GEYJ103V"))
      (libsource (lib "eagle-import") (part "sha2017_rev0_1_0_dev_R0603-DASHES"))
    )
    (comp (ref "R19")
      (value "5R")
      (footprint "eagle-import:R0603-DASHES")
      (fields (field (name "PARTNO") "ERJ-3GEYJ5R1V"))
      (libsource (lib "eagle-import") (part "sha2017_rev0_1_0_dev_R0603-DASHES"))
    )
    (comp (ref "R22")
      (value "10k")
      (footprint "eagle-import:R0603-DASHES")
      (fields (field (name "PARTNO") "ERJ-3GEYJ103V"))
      (libsource (lib "eagle-import") (part "sha2017_rev0_1_0_dev_R0603-DASHES"))
    )
    (comp (ref "R25")
      (value "10k")
      (footprint "eagle-import:R0603-DASHES")
      (fields (field (name "PARTNO") "ERJ-3GEYJ103V"))
      (libsource (lib "eagle-import") (part "sha2017_rev0_1_0_dev_R0603-DASHES"))
    )
    (comp (ref "R27")
      (value "10k")
      (footprint "eagle-import:R0603-DASHES")
      (fields (field (name "PARTNO") "ERJ-3GEYJ103V"))
      (libsource (lib "eagle-import") (part "R0603-DASHES"))
    )
    (comp (ref "R28")
      (value "10k")
      (footprint "eagle-import:R0603-DASHES")
      (fields (field (name "PARTNO") "ERJ-3GEYJ103V"))
      (libsource (lib "eagle-import") (part "R0603-DASHES"))
    )
    (comp (ref "R31")
      (value "100k")
      (footprint "eagle-import:R0603-DASHES")
      (fields (field (name "PARTNO") "ERJ-3GEYJ104V"))
      (libsource (lib "eagle-import") (part "sha2017_rev0_1_0_dev_R0603-DASHES"))
    )
    (comp (ref "S1")
      (value "SWITCH-MOMENTARY-2SMD")
      (footprint "eagle-import:TACTILE-SWITCH-SMD")
      (fields (field (name "PARTNO") "SKQGABE010"))
      (libsource (lib "eagle-import") (part "SWITCH-MOMENTARY-2SMD"))
    )
    (comp (ref "S2")
      (value "SWITCH-MOMENTARY-2SMD")
      (footprint "eagle-import:TACTILE-SWITCH-SMD")
      (fields (field (name "PARTNO") "SKQGABE010"))
      (libsource (lib "eagle-import") (part "SWITCH-MOMENTARY-2SMD"))
    )
    (comp (ref "T3")
      (value "MOSFET-PCHANNEL")
      (footprint "eagle-import:SOT23-3")
      (libsource (lib "eagle-import") (part "MOSFET-PCHANNEL"))
    )
    (comp (ref "TP103")
      (value "TEST-POINT3")
      (footprint "eagle-import:PAD.03X.03")
      (fields (field (name "PARTNO") "NAP"))
      (libsource (lib "eagle-import") (part "TEST-POINT3"))
    )
    (comp (ref "TP104")
      (value "TEST-POINT3")
      (footprint "eagle-import:PAD.03X.03")
      (fields (field (name "PARTNO") "NAP"))
      (libsource (lib "eagle-import") (part "TEST-POINT3"))
    )
    (comp (ref "TP105")
      (value "TEST-POINT3")
      (footprint "eagle-import:PAD.03X.03")
      (fields (field (name "PARTNO") "NAP"))
      (libsource (lib "eagle-import") (part "TEST-POINT3"))
    )
    (comp (ref "TP106")
      (value "TEST-POINT3")
      (footprint "eagle-import:PAD.03X.03")
      (fields (field (name "PARTNO") "NAP"))
      (libsource (lib "eagle-import") (part "TEST-POINT3"))
    )
    (comp (ref "TP107")
      (value "TEST-POINT3")
      (footprint "eagle-import:PAD.03X.03")
      (fields (field (name "PARTNO") "NAP"))
      (libsource (lib "eagle-import") (part "TEST-POINT3"))
    )
    (comp (ref "TP108")
      (value "TEST-POINT3")
      (footprint "eagle-import:PAD.03X.03")
      (fields (field (name "PARTNO") "NAP"))
      (libsource (lib "eagle-import") (part "TEST-POINT3"))
    )
    (comp (ref "TP109")
      (value "TEST-POINT3")
      (footprint "eagle-import:PAD.03X.03")
      (fields (field (name "PARTNO") "NAP"))
      (libsource (lib "eagle-import") (part "TEST-POINT3"))
    )
    (comp (ref "TP111")
      (value "TEST-POINT3")
      (footprint "eagle-import:PAD.03X.03")
      (fields (field (name "PARTNO") "NAP"))
      (libsource (lib "eagle-import") (part "TEST-POINT3"))
    )
    (comp (ref "TP113")
      (value "TEST-POINT3")
      (footprint "eagle-import:PAD.03X.03")
      (fields (field (name "PARTNO") "NAP"))
      (libsource (lib "eagle-import") (part "TEST-POINT3"))
    )
    (comp (ref "TP118")
      (value "TEST-POINT3")
      (footprint "eagle-import:PAD.03X.03")
      (fields (field (name "PARTNO") "NAP"))
      (libsource (lib "eagle-import") (part "TEST-POINT3"))
    )
    (comp (ref "TP123")
      (value "TEST-POINT3")
      (footprint "eagle-import:PAD.03X.03")
      (fields (field (name "PARTNO") "NAP"))
      (libsource (lib "eagle-import") (part "TEST-POINT3"))
    )
    (comp (ref "TP124")
      (value "TEST-POINT3")
      (footprint "eagle-import:PAD.03X.03")
      (fields (field (name "PARTNO") "NAP"))
      (libsource (lib "eagle-import") (part "TEST-POINT3"))
    )
    (comp (ref "TP125")
      (value "TEST-POINT3")
      (footprint "eagle-import:PAD.03X.03")
      (fields (field (name "PARTNO") "NAP"))
      (libsource (lib "eagle-import") (part "TEST-POINT3"))
    )
    (comp (ref "TP126")
      (value "TEST-POINT3")
      (footprint "eagle-import:PAD.03X.03")
      (fields (field (name "PARTNO") "NAP"))
      (libsource (lib "eagle-import") (part "TEST-POINT3"))
    )
    (comp (ref "TP127")
      (value "TEST-POINT3")
      (footprint "eagle-import:PAD.03X.03")
      (fields (field (name "PARTNO") "NAP"))
      (libsource (lib "eagle-import") (part "TEST-POINT3"))
    )
    (comp (ref "TP128")
      (value "TEST-POINT3")
      (footprint "eagle-import:PAD.03X.03")
      (fields (field (name "PARTNO") "NAP"))
      (libsource (lib "eagle-import") (part "TEST-POINT3"))
    )
    (comp (ref "TP130")
      (value "TEST-POINT3")
      (footprint "eagle-import:PAD.03X.03")
      (fields (field (name "PARTNO") "NAP"))
      (libsource (lib "eagle-import") (part "TEST-POINT3"))
    )
    (comp (ref "TP131")
      (value "TEST-POINT3")
      (footprint "eagle-import:PAD.03X.03")
      (fields (field (name "PARTNO") "NAP"))
      (libsource (lib "eagle-import") (part "TEST-POINT3"))
    )
    (comp (ref "TP132")
      (value "TEST-POINT3")
      (footprint "eagle-import:PAD.03X.03")
      (fields (field (name "PARTNO") "NAP"))
      (libsource (lib "eagle-import") (part "TEST-POINT3"))
    )
    (comp (ref "TP139")
      (value "TEST-POINT3")
      (footprint "eagle-import:PAD.03X.03")
      (fields (field (name "PARTNO") "NAP"))
      (libsource (lib "eagle-import") (part "TEST-POINT3"))
    )
    (comp (ref "USB1")
      (value "MOLEX-47346-0001")
      (footprint "eagle-import:MOLEX-47364-0001")
      (fields (field (name "PARTNO") "10118192-0001LF"))
      (libsource (lib "eagle-import") (part "MOLEX-47346-0001"))
    )
    (comp (ref "X1")
      (value "68712414022")
      (footprint "eagle-import:68712414022")
      (libsource (lib "eagle-import") (part "68712414022"))
    )
    (comp (ref "X2")
      (value "2908-05WB-MG")
      (footprint "eagle-import:MICRO-SD-SOCKET-PP")
      (libsource (lib "eagle-import") (part "2908-05WB-MG"))
    )
  )
  (nets
    (net (code "1") (name "+3V3") (class "Default")
      (node (ref "C17") (pin "1") (pinfunction "1_1") (pintype "passive"))
      (node (ref "C20") (pin "1") (pinfunction "1_1") (pintype "passive"))
      (node (ref "C22") (pin "1") (pinfunction "1_1") (pintype "passive"))
      (node (ref "C26") (pin "1") (pinfunction "1_1") (pintype "passive"))
      (node (ref "C27") (pin "1") (pinfunction "1_1") (pintype "passive"))
      (node (ref "C30") (pin "1") (pinfunction "1_1") (pintype "passive"))
      (node (ref "C37") (pin "1") (pinfunction "1_1") (pintype "passive"))
      (node (ref "C39") (pin "1") (pinfunction "1_1") (pintype "passive"))
      (node (ref "C43") (pin "1") (pinfunction "1_1") (pintype "passive"))
      (node (ref "C44") (pin "1") (pinfunction "1_1") (pintype "passive"))
      (node (ref "IC2") (pin "4") (pinfunction "OUT_4") (pintype "passive"))
      (node (ref "IC3") (pin "2") (pinfunction "VCC_2") (pintype "power_in"))
      (node (ref "L1") (pin "1") (pinfunction "1_1") (pintype "passive"))
      (node (ref "R1") (pin "2") (pinfunction "2_2") (pintype "passive"))
      (node (ref "R16") (pin "2") (pinfunction "2_2") (pintype "passive"))
      (node (ref "R22") (pin "1") (pinfunction "1_1") (pintype "passive"))
      (node (ref "R23") (pin "1") (pinfunction "1_1") (pintype "passive"))
      (node (ref "R24") (pin "1") (pinfunction "1_1") (pintype "passive"))
      (node (ref "R28") (pin "2") (pinfunction "2_2") (pintype "passive"))
      (node (ref "R36") (pin "2") (pinfunction "2_2") (pintype "passive"))
      (node (ref "T3") (pin "2") (pinfunction "S_2") (pintype "passive"))
      (node (ref "TP119") (pin "P$1") (pinfunction "1_P$1") (pintype "bidirectional"))
      (node (ref "U1") (pin "20") (pinfunction "V_DD_20") (pintype "power_in"))
      (node (ref "X1") (pin "10") (pinfunction "10_10") (pintype "passive"))
      (node (ref "X1") (pin "7") (pinfunction "7_7") (pintype "passive"))
      (node (ref "X1") (pin "9") (pinfunction "9_9") (pintype "passive"))
    )
    (net (code "2") (name "+5V") (class "Default")
      (node (ref "C11") (pin "1") (pinfunction "1_1") (pintype "passive"))
      (node (ref "C9") (pin "1") (pinfunction "1_1") (pintype "passive"))
      (node (ref "D1") (pin "C") (pinfunction "C_C") (pintype "passive"))
      (node (ref "D3") (pin "A") (pinfunction "A_A") (pintype "passive"))
      (node (ref "F1") (pin "2") (pinfunction "2_2") (pintype "bidirectional"))
      (node (ref "IC1") (pin "7") (pinfunction "REGIN_7") (pintype "passive"))
      (node (ref "IC1") (pin "8") (pinfunction "VBUS_8") (pintype "input"))
      (node (ref "R30") (pin "1") (pinfunction "1_1") (pintype "passive"))
      (node (ref "R4") (pin "2") (pinfunction "2_2") (pintype "passive"))
      (node (ref "R7") (pin "2") (pinfunction "2_2") (pintype "passive"))
      (node (ref "T1") (pin "1") (pinfunction "G_1") (pintype "passive"))
      (node (ref "TP112") (pin "P$1") (pinfunction "1_P$1") (pintype "bidirectional"))
    )
    (net (code "3") (name "3V3_SWITCHED") (class "Default")
      (node (ref "C12") (pin "1") (pinfunction "1_1") (pintype "passive"))
      (node (ref "C31") (pin "1") (pinfunction "1_1") (pintype "passive"))
      (node (ref "C40") (pin "1") (pinfunction "1_1") (pintype "passive"))
      (node (ref "C41") (pin "1") (pinfunction "1_1") (pintype "passive"))
      (node (ref "C7") (pin "1") (pinfunction "1_1") (pintype "passive"))
      (node (ref "R17") (pin "2") (pinfunction "2_2") (pintype "passive"))
      (node (ref "R25") (pin "2") (pinfunction "2_2") (pintype "passive"))
      (node (ref "R31") (pin "1") (pinfunction "1_1") (pintype "passive"))
      (node (ref "R5") (pin "2") (pinfunction "2_2") (pintype "passive"))
      (node (ref "R8") (pin "2") (pinfunction "2_2") (pintype "passive"))
      (node (ref "T3") (pin "3") (pinfunction "D_3") (pintype "passive"))
      (node (ref "TP116") (pin "P$1") (pinfunction "1_P$1") (pintype "bidirectional"))
      (node (ref "X2") (pin "4") (pinfunction "VCC_4") (pintype "bidirectional"))
      (node (ref "X3") (pin "12") (pinfunction "1_12") (pintype "passive"))
    )
    (net (code "4") (name "CHRG_STAT") (class "Default")
      (node (ref "IC4") (pin "7") (pinfunction "CHRG_7") (pintype "bidirectional"))
      (node (ref "R36") (pin "1") (pinfunction "1_1") (pintype "passive"))
      (node (ref "U1") (pin "17") (pinfunction "ELE9_17") (pintype "output"))
    )
    (net (code "5") (name "ESP32_FLASH") (class "Default")
      (node (ref "D2") (pin "C") (pinfunction "C_C") (pintype "passive"))
      (node (ref "IC3") (pin "25") (pinfunction "IO0_25") (pintype "bidirectional"))
      (node (ref "Q4") (pin "3") (pinfunction "C_3") (pintype "passive"))
      (node (ref "R16") (pin "1") (pinfunction "1_1") (pintype "passive"))
      (node (ref "S2") (pin "3") (pinfunction "2_3") (pintype "passive"))
      (node (ref "TP120") (pin "P$1") (pinfunction "1_P$1") (pintype "bidirectional"))
    )
    (net (code "6") (name "ESP32_RX") (class "Default")
      (node (ref "D4") (pin "C") (pinfunction "C_C") (pintype "passive"))
      (node (ref "IC1") (pin "26") (pinfunction "TXD_26") (pintype "output"))
      (node (ref "IC3") (pin "34") (pinfunction "RXD0_34") (pintype "bidirectional"))
      (node (ref "TP133") (pin "P$1") (pinfunction "1_P$1") (pintype "bidirectional"))
    )
    (net (code "7") (name "ESP32_TX") (class "Default")
      (node (ref "D5") (pin "C") (pinfunction "C_C") (pintype "passive"))
      (node (ref "IC1") (pin "25") (pinfunction "RXD_25") (pintype "input"))
      (node (ref "IC3") (pin "35") (pinfunction "TXD0_35") (pintype "bidirectional"))
      (node (ref "TP134") (pin "P$1") (pinfunction "1_P$1") (pintype "bidirectional"))
    )
    (net (code "8") (name "ESP32_~{RESET}") (class "Default")
      (node (ref "IC3") (pin "3") (pinfunction "EN_3") (pintype "bidirectional"))
      (node (ref "Q3") (pin "3") (pinfunction "C_3") (pintype "passive"))
      (node (ref "R22") (pin "2") (pinfunction "2_2") (pintype "passive"))
      (node (ref "S1") (pin "3") (pinfunction "2_3") (pintype "passive"))
      (node (ref "TP121") (pin "P$1") (pinfunction "1_P$1") (pintype "bidirectional"))
    )
    (net (code "9") (name "EXTIO-0") (class "Default")
      (node (ref "IC3") (pin "9") (pinfunction "IO33_9") (pintype "bidirectional"))
      (node (ref "X3") (pin "3") (pinfunction "10_3") (pintype "passive"))
    )
    (net (code "10") (name "EXTIO-1") (class "Default")
      (node (ref "IC3") (pin "27") (pinfunction "IO16_27") (pintype "bidirectional"))
      (node (ref "X3") (pin "4") (pinfunction "9_4") (pintype "passive"))
    )
    (net (code "11") (name "EXTIO-2") (class "Default")
      (node (ref "IC3") (pin "28") (pinfunction "IO17_28") (pintype "bidirectional"))
      (node (ref "X3") (pin "5") (pinfunction "8_5") (pintype "passive"))
    )
    (net (code "12") (name "EXTIO-3") (class "Default")
      (node (ref "IC3") (pin "26") (pinfunction "IO4_26") (pintype "bidirectional"))
      (node (ref "X3") (pin "9") (pinfunction "4_9") (pintype "passive"))
    )
    (net (code "13") (name "EXTIO-4") (class "Default")
      (node (ref "IC3") (pin "14") (pinfunction "IO12_14") (pintype "bidirectional"))
      (node (ref "X3") (pin "10") (pinfunction "3_10") (pintype "passive"))
    )
    (net (code "14") (name "GDR") (class "Default")
      (node (ref "Q5") (pin "1") (pinfunction "G_1") (pintype "passive"))
      (node (ref "TP124") (pin "P$1") (pinfunction "1_P$1") (pintype "bidirectional"))
      (node (ref "X1") (pin "23") (pinfunction "23_23") (pintype "passive"))
    )
    (net (code "15") (name "GND") (class "Default")
      (node (ref "$$U$1") (pin "P$1") (pinfunction "P$1_P$1") (pintype "bidirectional"))
      (node (ref "$$U$2") (pin "P$1") (pinfunction "P$1_P$1") (pintype "bidirectional"))
      (node (ref "$$U$3") (pin "P$1") (pinfunction "P$1_P$1") (pintype "bidirectional"))
      (node (ref "$$U$4") (pin "P$1") (pinfunction "P$1_P$1") (pintype "bidirectional"))
      (node (ref "$$U$5") (pin "P$1") (pinfunction "P$1_P$1") (pintype "bidirectional"))
      (node (ref "$$U$6") (pin "P$1") (pinfunction "P$1_P$1") (pintype "bidirectional"))
      (node (ref "$$U$7") (pin "P$1") (pinfunction "P$1_P$1") (pintype "bidirectional"))
      (node (ref "$$U$8") (pin "P$1") (pinfunction "P$1_P$1") (pintype "bidirectional"))
      (node (ref "$$U$9") (pin "P$1") (pinfunction "P$1_P$1") (pintype "bidirectional"))
      (node (ref "C1") (pin "1") (pinfunction "1_1") (pintype "passive"))
      (node (ref "C10") (pin "2") (pinfunction "2_2") (pintype "passive"))
      (node (ref "C11") (pin "2") (pinfunction "2_2") (pintype "passive"))
      (node (ref "C12") (pin "2") (pinfunction "2_2") (pintype "passive"))
      (node (ref "C13") (pin "2") (pinfunction "2_2") (pintype "passive"))
      (node (ref "C14") (pin "2") (pinfunction "2_2") (pintype "passive"))
      (node (ref "C15") (pin "2") (pinfunction "2_2") (pintype "passive"))
      (node (ref "C16") (pin "2") (pinfunction "2_2") (pintype "passive"))
      (node (ref "C17") (pin "2") (pinfunction "2_2") (pintype "passive"))
      (node (ref "C18") (pin "2") (pinfunction "2_2") (pintype "passive"))
      (node (ref "C19") (pin "1") (pinfunction "1_1") (pintype "passive"))
      (node (ref "C2") (pin "1") (pinfunction "1_1") (pintype "passive"))
      (node (ref "C20") (pin "2") (pinfunction "2_2") (pintype "passive"))
      (node (ref "C21") (pin "1") (pinfunction "1_1") (pintype "passive"))
      (node (ref "C22") (pin "2") (pinfunction "2_2") (pintype "passive"))
      (node (ref "C23") (pin "1") (pinfunction "1_1") (pintype "passive"))
      (node (ref "C24") (pin "2") (pinfunction "2_2") (pintype "passive"))
      (node (ref "C26") (pin "2") (pinfunction "2_2") (pintype "passive"))
      (node (ref "C27") (pin "2") (pinfunction "2_2") (pintype "passive"))
      (node (ref "C28") (pin "1") (pinfunction "1_1") (pintype "passive"))
      (node (ref "C29") (pin "1") (pinfunction "1_1") (pintype "passive"))
      (node (ref "C3") (pin "1") (pinfunction "1_1") (pintype "passive"))
      (node (ref "C30") (pin "2") (pinfunction "2_2") (pintype "passive"))
      (node (ref "C31") (pin "2") (pinfunction "2_2") (pintype "passive"))
      (node (ref "C32") (pin "1") (pinfunction "1_1") (pintype "passive"))
      (node (ref "C33") (pin "1") (pinfunction "1_1") (pintype "passive"))
      (node (ref "C34") (pin "2") (pinfunction "2_2") (pintype "passive"))
      (node (ref "C35") (pin "1") (pinfunction "1_1") (pintype "passive"))
      (node (ref "C36") (pin "1") (pinfunction "1_1") (pintype "passive"))
      (node (ref "C37") (pin "2") (pinfunction "2_2") (pintype "passive"))
      (node (ref "C38") (pin "1") (pinfunction "1_1") (pintype "passive"))
      (node (ref "C39") (pin "2") (pinfunction "2_2") (pintype "passive"))
      (node (ref "C4") (pin "1") (pinfunction "1_1") (pintype "passive"))
      (node (ref "C40") (pin "2") (pinfunction "2_2") (pintype "passive"))
      (node (ref "C41") (pin "2") (pinfunction "2_2") (pintype "passive"))
      (node (ref "C43") (pin "2") (pinfunction "2_2") (pintype "passive"))
      (node (ref "C44") (pin "2") (pinfunction "2_2") (pintype "passive"))
      (node (ref "C45") (pin "2") (pinfunction "2_2") (pintype "passive"))
      (node (ref "C5") (pin "1") (pinfunction "1_1") (pintype "passive"))
      (node (ref "C6") (pin "1") (pinfunction "1_1") (pintype "passive"))
      (node (ref "C7") (pin "2") (pinfunction "2_2") (pintype "passive"))
      (node (ref "C8") (pin "2") (pinfunction "2_2") (pintype "passive"))
      (node (ref "C9") (pin "2") (pinfunction "2_2") (pintype "passive"))
      (node (ref "D1") (pin "A") (pinfunction "A_A") (pintype "passive"))
      (node (ref "D100") (pin "3") (pinfunction "VSS_3") (pintype "power_in"))
      (node (ref "D101") (pin "3") (pinfunction "VSS_3") (pintype "power_in"))
      (node (ref "D102") (pin "3") (pinfunction "VSS_3") (pintype "power_in"))
      (node (ref "D103") (pin "3") (pinfunction "VSS_3") (pintype "power_in"))
      (node (ref "D104") (pin "3") (pinfunction "VSS_3") (pintype "power_in"))
      (node (ref "D105") (pin "3") (pinfunction "VSS_3") (pintype "power_in"))
      (node (ref "D6") (pin "C") (pinfunction "C_C") (pintype "passive"))
      (node (ref "D7") (pin "C") (pinfunction "C_C") (pintype "passive"))
      (node (ref "IC1") (pin "3") (pinfunction "GND_3") (pintype "power_in"))
      (node (ref "IC1") (pin "EXP") (pinfunction "GND_EXP") (pintype "power_in"))
      (node (ref "IC1") (pin "M") (pinfunction "GND_M") (pintype "power_in"))
      (node (ref "IC2") (pin "1") (pinfunction "ADJ_1") (pintype "input"))
      (node (ref "IC3") (pin "0") (pinfunction "GND_0") (pintype "power_in"))
      (node (ref "IC3") (pin "1") (pinfunction "GND_1") (pintype "power_in"))
      (node (ref "IC3") (pin "15") (pinfunction "GND_15") (pintype "power_in"))
      (node (ref "IC3") (pin "38") (pinfunction "GND_38") (pintype "power_in"))
      (node (ref "IC4") (pin "3") (pinfunction "GND_3") (pintype "bidirectional"))
      (node (ref "Q1") (pin "2") (pinfunction "E_2") (pintype "passive"))
      (node (ref "Q2") (pin "2") (pinfunction "E_2") (pintype "passive"))
      (node (ref "Q6") (pin "2") (pinfunction "E_2") (pintype "passive"))
      (node (ref "R19") (pin "2") (pinfunction "2_2") (pintype "passive"))
      (node (ref "R20") (pin "1") (pinfunction "1_1") (pintype "passive"))
      (node (ref "R35") (pin "2") (pinfunction "2_2") (pintype "passive"))
      (node (ref "R37") (pin "1") (pinfunction "1_1") (pintype "passive"))
      (node (ref "R4") (pin "1") (pinfunction "1_1") (pintype "passive"))
      (node (ref "R6") (pin "1") (pinfunction "1_1") (pintype "passive"))
      (node (ref "S1") (pin "1") (pinfunction "1_1") (pintype "passive"))
      (node (ref "S2") (pin "1") (pinfunction "1_1") (pintype "passive"))
      (node (ref "SJ3") (pin "1") (pinfunction "1_1") (pintype "passive"))
      (node (ref "TP1") (pin "P$1") (pinfunction "1_P$1") (pintype "bidirectional"))
      (node (ref "TP102") (pin "P$1") (pinfunction "1_P$1") (pintype "bidirectional"))
      (node (ref "TP103") (pin "P$1") (pinfunction "1_P$1") (pintype "bidirectional"))
      (node (ref "TP106") (pin "P$1") (pinfunction "1_P$1") (pintype "bidirectional"))
      (node (ref "TP122") (pin "P$1") (pinfunction "1_P$1") (pintype "bidirectional"))
      (node (ref "TP125") (pin "P$1") (pinfunction "1_P$1") (pintype "bidirectional"))
      (node (ref "TP135") (pin "P$1") (pinfunction "1_P$1") (pintype "bidirectional"))
      (node (ref "TP140") (pin "P$1") (pinfunction "1_P$1") (pintype "bidirectional"))
      (node (ref "U$10") (pin "P$1") (pinfunction "P$1_P$1") (pintype "bidirectional"))
      (node (ref "U$11") (pin "P$1") (pinfunction "P$1_P$1") (pintype "bidirectional"))
      (node (ref "U$12") (pin "P$1") (pinfunction "P$1_P$1") (pintype "bidirectional"))
      (node (ref "U$13") (pin "P$1") (pinfunction "P$1_P$1") (pintype "bidirectional"))
      (node (ref "U$14") (pin "P$1") (pinfunction "P$1_P$1") (pintype "bidirectional"))
      (node (ref "U$15") (pin "P$1") (pinfunction "P$1_P$1") (pintype "bidirectional"))
      (node (ref "U$16") (pin "P$1") (pinfunction "P$1_P$1") (pintype "bidirectional"))
      (node (ref "U$17") (pin "P$1") (pinfunction "P$1_P$1") (pintype "bidirectional"))
      (node (ref "U$18") (pin "P$1") (pinfunction "P$1_P$1") (pintype "bidirectional"))
      (node (ref "U$19") (pin "P$1") (pinfunction "P$1_P$1") (pintype "bidirectional"))
      (node (ref "U$2") (pin "P$1") (pinfunction "P$1_P$1") (pintype "bidirectional"))
      (node (ref "U$20") (pin "P$1") (pinfunction "P$1_P$1") (pintype "bidirectional"))
      (node (ref "U$21") (pin "P$1") (pinfunction "P$1_P$1") (pintype "bidirectional"))
      (node (ref "U$22") (pin "P$1") (pinfunction "P$1_P$1") (pintype "bidirectional"))
      (node (ref "U$23") (pin "P$1") (pinfunction "P$1_P$1") (pintype "bidirectional"))
      (node (ref "U$3") (pin "P$1") (pinfunction "P$1_P$1") (pintype "bidirectional"))
      (node (ref "U$4") (pin "P$1") (pinfunction "P$1_P$1") (pintype "bidirectional"))
      (node (ref "U$5") (pin "P$1") (pinfunction "P$1_P$1") (pintype "bidirectional"))
      (node (ref "U$6") (pin "P$1") (pinfunction "P$1_P$1") (pintype "bidirectional"))
      (node (ref "U1") (pin "4") (pinfunction "ADDR_4") (pintype "input"))
      (node (ref "U1") (pin "6") (pinfunction "V_SS_6") (pintype "power_in"))
      (node (ref "USB1") (pin "5") (pinfunction "5_5") (pintype "input"))
      (node (ref "USB1") (pin "GND1") (pinfunction "GND1_GND1") (pintype "bidirectional"))
      (node (ref "USB1") (pin "GND2") (pinfunction "GND2_GND2") (pintype "bidirectional"))
      (node (ref "USB1") (pin "GND3") (pinfunction "GND3_GND3") (pintype "bidirectional"))
      (node (ref "USB1") (pin "GND4") (pinfunction "GND4_GND4") (pintype "bidirectional"))
      (node (ref "X1") (pin "17") (pinfunction "17_17") (pintype "passive"))
      (node (ref "X1") (pin "8") (pinfunction "8_8") (pintype "passive"))
      (node (ref "X2") (pin "6") (pinfunction "GND_6") (pintype "bidirectional"))
      (node (ref "X2") (pin "CD2") (pinfunction "SHIELD_CD2") (pintype "bidirectional"))
      (node (ref "X2") (pin "GND1") (pinfunction "SHIELD_GND1") (pintype "bidirectional"))
      (node (ref "X2") (pin "GND3") (pinfunction "SHIELD_GND3") (pintype "bidirectional"))
      (node (ref "X3") (pin "1") (pinfunction "12_1") (pintype "passive"))
      (node (ref "X3") (pin "11") (pinfunction "2_11") (pintype "passive"))
      (node (ref "X4") (pin "2") (pinfunction "1_2") (pintype "passive"))
    )
    (net (code "16") (name "I2C_INT") (class "Default")
      (node (ref "IC3") (pin "10") (pinfunction "IO25_10") (pintype "bidirectional"))
      (node (ref "R1") (pin "1") (pinfunction "1_1") (pintype "passive"))
      (node (ref "U1") (pin "1") (pinfunction "~{IRQ}_1") (pintype "input"))
    )
    (net (code "17") (name "I2C_SCL") (class "Default")
      (node (ref "IC3") (pin "12") (pinfunction "IO27_12") (pintype "bidirectional"))
      (node (ref "R24") (pin "2") (pinfunction "2_2") (pintype "passive"))
      (node (ref "TP100") (pin "P$1") (pinfunction "1_P$1") (pintype "bidirectional"))
      (node (ref "TP114") (pin "P$1") (pinfunction "1_P$1") (pintype "bidirectional"))
      (node (ref "TP3") (pin "P$1") (pinfunction "1_P$1") (pintype "bidirectional"))
      (node (ref "U1") (pin "2") (pinfunction "SCL_2") (pintype "input"))
      (node (ref "X3") (pin "6") (pinfunction "7_6") (pintype "passive"))
    )
    (net (code "18") (name "I2C_SDA") (class "Default")
      (node (ref "IC3") (pin "11") (pinfunction "IO26_11") (pintype "bidirectional"))
      (node (ref "R23") (pin "2") (pinfunction "2_2") (pintype "passive"))
      (node (ref "TP101") (pin "P$1") (pinfunction "1_P$1") (pintype "bidirectional"))
      (node (ref "TP115") (pin "P$1") (pinfunction "1_P$1") (pintype "bidirectional"))
      (node (ref "TP2") (pin "P$1") (pinfunction "1_P$1") (pintype "bidirectional"))
      (node (ref "U1") (pin "3") (pinfunction "SDA_3") (pintype "input"))
      (node (ref "X3") (pin "7") (pinfunction "6_7") (pintype "passive"))
    )
    (net (code "19") (name "LCD_BUSY") (class "Default")
      (node (ref "IC3") (pin "36") (pinfunction "IO22_36") (pintype "bidirectional"))
      (node (ref "TP118") (pin "P$1") (pinfunction "1_P$1") (pintype "bidirectional"))
      (node (ref "X1") (pin "16") (pinfunction "16_16") (pintype "passive"))
    )
    (net (code "20") (name "LCD_CS") (class "Default")
      (node (ref "IC3") (pin "31") (pinfunction "IO19_31") (pintype "bidirectional"))
      (node (ref "TP109") (pin "P$1") (pinfunction "1_P$1") (pintype "bidirectional"))
      (node (ref "X1") (pin "13") (pinfunction "13_13") (pintype "passive"))
    )
    (net (code "21") (name "LCD_D{slash}~{S}") (class "Default")
      (node (ref "IC3") (pin "33") (pinfunction "IO21_33") (pintype "bidirectional"))
      (node (ref "TP111") (pin "P$1") (pinfunction "1_P$1") (pintype "bidirectional"))
      (node (ref "X1") (pin "14") (pinfunction "14_14") (pintype "passive"))
    )
    (net (code "22") (name "LCD_MOSI") (class "Default")
      (node (ref "IC3") (pin "29") (pinfunction "IO5_29") (pintype "bidirectional"))
      (node (ref "TP107") (pin "P$1") (pinfunction "1_P$1") (pintype "bidirectional"))
      (node (ref "X1") (pin "11") (pinfunction "11_11") (pintype "passive"))
    )
    (net (code "23") (name "LCD_SCK") (class "Default")
      (node (ref "IC3") (pin "30") (pinfunction "IO18_30") (pintype "bidirectional"))
      (node (ref "TP108") (pin "P$1") (pinfunction "1_P$1") (pintype "bidirectional"))
      (node (ref "X1") (pin "12") (pinfunction "12_12") (pintype "passive"))
    )
    (net (code "24") (name "LCD_~{RESET}") (class "Default")
      (node (ref "IC3") (pin "37") (pinfunction "IO23_37") (pintype "bidirectional"))
      (node (ref "TP113") (pin "P$1") (pinfunction "1_P$1") (pintype "bidirectional"))
      (node (ref "X1") (pin "15") (pinfunction "15_15") (pintype "passive"))
    )
    (net (code "25") (name "Net-(C25-Pad1)") (class "Default")
      (node (ref "C25") (pin "1") (pinfunction "1_1") (pintype "passive"))
      (node (ref "D7") (pin "A") (pinfunction "A_A") (pintype "passive"))
      (node (ref "D8") (pin "C") (pinfunction "C_C") (pintype "passive"))
    )
    (net (code "26") (name "Net-(D4-PadA)") (class "Default")
      (node (ref "D4") (pin "A") (pinfunction "A_A") (pintype "passive"))
      (node (ref "R3") (pin "1") (pinfunction "1_1") (pintype "passive"))
    )
    (net (code "27") (name "Net-(D5-PadA)") (class "Default")
      (node (ref "D5") (pin "A") (pinfunction "A_A") (pintype "passive"))
      (node (ref "R14") (pin "1") (pinfunction "1_1") (pintype "passive"))
    )
    (net (code "28") (name "Net-(D6-PadA)") (class "Default")
      (node (ref "D6") (pin "A") (pinfunction "A_A") (pintype "passive"))
      (node (ref "R12") (pin "1") (pinfunction "1_1") (pintype "passive"))
    )
    (net (code "29") (name "Net-(D100-DIN)") (class "Default")
      (node (ref "D100") (pin "4") (pinfunction "DIN_4") (pintype "input"))
      (node (ref "D101") (pin "2") (pinfunction "DOUT_2") (pintype "output"))
    )
    (net (code "30") (name "Net-(D101-DIN)") (class "Default")
      (node (ref "D101") (pin "4") (pinfunction "DIN_4") (pintype "input"))
      (node (ref "D102") (pin "2") (pinfunction "DOUT_2") (pintype "output"))
    )
    (net (code "31") (name "Net-(D102-DIN)") (class "Default")
      (node (ref "D102") (pin "4") (pinfunction "DIN_4") (pintype "input"))
      (node (ref "D103") (pin "2") (pinfunction "DOUT_2") (pintype "output"))
    )
    (net (code "32") (name "Net-(D103-DIN)") (class "Default")
      (node (ref "D103") (pin "4") (pinfunction "DIN_4") (pintype "input"))
      (node (ref "D104") (pin "2") (pinfunction "DOUT_2") (pintype "output"))
    )
    (net (code "33") (name "Net-(D104-DIN)") (class "Default")
      (node (ref "D104") (pin "4") (pinfunction "DIN_4") (pintype "input"))
      (node (ref "D105") (pin "2") (pinfunction "DOUT_2") (pintype "output"))
    )
    (net (code "34") (name "Net-(IC1-DTR)") (class "Default")
      (node (ref "IC1") (pin "28") (pinfunction "DTR_28") (pintype "output"))
      (node (ref "Q4") (pin "2") (pinfunction "E_2") (pintype "passive"))
      (node (ref "R18") (pin "1") (pinfunction "1_1") (pintype "passive"))
    )
    (net (code "35") (name "Net-(IC1-RTS)") (class "Default")
      (node (ref "IC1") (pin "24") (pinfunction "RTS_24") (pintype "output"))
      (node (ref "Q3") (pin "2") (pinfunction "E_2") (pintype "passive"))
      (node (ref "R15") (pin "1") (pinfunction "1_1") (pintype "passive"))
    )
    (net (code "36") (name "Net-(IC1-~{RST})") (class "Default")
      (node (ref "IC1") (pin "9") (pinfunction "~{RST}_9") (pintype "bidirectional"))
      (node (ref "R13") (pin "2") (pinfunction "2_2") (pintype "passive"))
    )
    (net (code "37") (name "Net-(IC3-CLK)") (class "Default")
      (node (ref "IC3") (pin "20") (pinfunction "CLK_20") (pintype "bidirectional"))
      (node (ref "TP130") (pin "P$1") (pinfunction "1_P$1") (pintype "bidirectional"))
    )
    (net (code "38") (name "Net-(IC3-CND)") (class "Default")
      (node (ref "IC3") (pin "19") (pinfunction "CND_19") (pintype "bidirectional"))
      (node (ref "TP128") (pin "P$1") (pinfunction "1_P$1") (pintype "bidirectional"))
    )
    (net (code "39") (name "Net-(IC3-SD0)") (class "Default")
      (node (ref "IC3") (pin "21") (pinfunction "SD0_21") (pintype "bidirectional"))
      (node (ref "TP131") (pin "P$1") (pinfunction "1_P$1") (pintype "bidirectional"))
    )
    (net (code "40") (name "Net-(IC3-SD1)") (class "Default")
      (node (ref "IC3") (pin "22") (pinfunction "SD1_22") (pintype "bidirectional"))
      (node (ref "TP132") (pin "P$1") (pinfunction "1_P$1") (pintype "bidirectional"))
    )
    (net (code "41") (name "Net-(IC3-SD2)") (class "Default")
      (node (ref "IC3") (pin "17") (pinfunction "SD2_17") (pintype "bidirectional"))
      (node (ref "TP126") (pin "P$1") (pinfunction "1_P$1") (pintype "bidirectional"))
    )
    (net (code "42") (name "Net-(IC3-SD3)") (class "Default")
      (node (ref "IC3") (pin "18") (pinfunction "SD3_18") (pintype "bidirectional"))
      (node (ref "TP127") (pin "P$1") (pinfunction "1_P$1") (pintype "bidirectional"))
    )
    (net (code "43") (name "Net-(IC3-SENSOR_VN)") (class "Default")
      (node (ref "C29") (pin "2") (pinfunction "2_2") (pintype "passive"))
      (node (ref "IC3") (pin "5") (pinfunction "SENSOR_VN_5") (pintype "bidirectional"))
    )
    (net (code "44") (name "Net-(IC3-SENSOR_VP)") (class "Default")
      (node (ref "C28") (pin "2") (pinfunction "2_2") (pintype "passive"))
      (node (ref "IC3") (pin "4") (pinfunction "SENSOR_VP_4") (pintype "bidirectional"))
    )
    (net (code "45") (name "Net-(IC4-BAT)") (class "Default")
      (node (ref "C34") (pin "1") (pinfunction "1_1") (pintype "passive"))
      (node (ref "F2") (pin "1") (pinfunction "1_1") (pintype "bidirectional"))
      (node (ref "IC4") (pin "5") (pinfunction "BAT_5") (pintype "bidirectional"))
      (node (ref "X4") (pin "3") (pinfunction "1_3") (pintype "passive"))
    )
    (net (code "46") (name "Net-(IC4-CE)") (class "Default")
      (node (ref "C23") (pin "2") (pinfunction "2_2") (pintype "passive"))
      (node (ref "C24") (pin "1") (pinfunction "1_1") (pintype "passive"))
      (node (ref "IC4") (pin "4") (pinfunction "VCC_4") (pintype "bidirectional"))
      (node (ref "IC4") (pin "8") (pinfunction "CE_8") (pintype "bidirectional"))
      (node (ref "R30") (pin "2") (pinfunction "2_2") (pintype "passive"))
      (node (ref "R32") (pin "2") (pinfunction "2_2") (pintype "passive"))
    )
    (net (code "47") (name "Net-(IC4-PROG)") (class "Default")
      (node (ref "IC4") (pin "2") (pinfunction "PROG_2") (pintype "bidirectional"))
      (node (ref "R29") (pin "1") (pinfunction "1_1") (pintype "passive"))
    )
    (net (code "48") (name "Net-(M1-Pad+)") (class "Default")
      (node (ref "M1") (pin "+") (pinfunction "+_+") (pintype "bidirectional"))
      (node (ref "R2") (pin "1") (pinfunction "1_1") (pintype "passive"))
    )
    (net (code "49") (name "Net-(Q1-B)") (class "Default")
      (node (ref "Q1") (pin "1") (pinfunction "B_1") (pintype "passive"))
      (node (ref "R10") (pin "2") (pinfunction "2_2") (pintype "passive"))
    )
    (net (code "50") (name "Net-(Q1-C)") (class "Default")
      (node (ref "Q1") (pin "3") (pinfunction "C_3") (pintype "passive"))
      (node (ref "R9") (pin "1") (pinfunction "1_1") (pintype "passive"))
      (node (ref "T2") (pin "1") (pinfunction "G_1") (pintype "passive"))
    )
    (net (code "51") (name "Net-(Q2-B)") (class "Default")
      (node (ref "Q2") (pin "1") (pinfunction "B_1") (pintype "passive"))
      (node (ref "R11") (pin "1") (pinfunction "1_1") (pintype "passive"))
    )
    (net (code "52") (name "Net-(Q2-C)") (class "Default")
      (node (ref "M1") (pin "-") (pinfunction "-_-") (pintype "bidirectional"))
      (node (ref "Q2") (pin "3") (pinfunction "C_3") (pintype "passive"))
    )
    (net (code "53") (name "Net-(Q3-B)") (class "Default")
      (node (ref "Q3") (pin "1") (pinfunction "B_1") (pintype "passive"))
      (node (ref "R18") (pin "2") (pinfunction "2_2") (pintype "passive"))
    )
    (net (code "54") (name "Net-(Q4-B)") (class "Default")
      (node (ref "Q4") (pin "1") (pinfunction "B_1") (pintype "passive"))
      (node (ref "R15") (pin "2") (pinfunction "2_2") (pintype "passive"))
    )
    (net (code "55") (name "Net-(Q5-D)") (class "Default")
      (node (ref "C25") (pin "2") (pinfunction "2_2") (pintype "passive"))
      (node (ref "D9") (pin "A") (pinfunction "A_A") (pintype "passive"))
      (node (ref "L1") (pin "2") (pinfunction "2_2") (pintype "passive"))
      (node (ref "Q5") (pin "3") (pinfunction "D_3") (pintype "passive"))
    )
    (net (code "56") (name "Net-(Q6-B)") (class "Default")
      (node (ref "Q6") (pin "1") (pinfunction "B_1") (pintype "passive"))
      (node (ref "R27") (pin "2") (pinfunction "2_2") (pintype "passive"))
    )
    (net (code "57") (name "Net-(Q6-C)") (class "Default")
      (node (ref "Q6") (pin "3") (pinfunction "C_3") (pintype "passive"))
      (node (ref "R28") (pin "1") (pinfunction "1_1") (pintype "passive"))
      (node (ref "T3") (pin "1") (pinfunction "G_1") (pintype "passive"))
    )
    (net (code "58") (name "Net-(R29-Pad2)") (class "Default")
      (node (ref "R29") (pin "2") (pinfunction "2_2") (pintype "passive"))
      (node (ref "R35") (pin "1") (pinfunction "1_1") (pintype "passive"))
      (node (ref "SJ3") (pin "2") (pinfunction "2_2") (pintype "passive"))
    )
    (net (code "59") (name "Net-(TOUCH_SEL-DOWN)") (class "Default")
      (node (ref "TOUCH_SEL") (pin "D") (pinfunction "DOWN_D") (pintype "bidirectional"))
      (node (ref "U1") (pin "12") (pinfunction "ELE4_12") (pintype "output"))
    )
    (net (code "60") (name "Net-(TOUCH_SEL-LEFT)") (class "Default")
      (node (ref "TOUCH_SEL") (pin "L") (pinfunction "LEFT_L") (pintype "bidirectional"))
      (node (ref "U1") (pin "15") (pinfunction "ELE7_15") (pintype "output"))
    )
    (net (code "61") (name "Net-(TOUCH_SEL-RIGHT)") (class "Default")
      (node (ref "TOUCH_SEL") (pin "R") (pinfunction "RIGHT_R") (pintype "bidirectional"))
      (node (ref "U1") (pin "13") (pinfunction "ELE5_13") (pintype "output"))
    )
    (net (code "62") (name "Net-(TP139-1)") (class "Default")
      (node (ref "F1") (pin "1") (pinfunction "1_1") (pintype "bidirectional"))
      (node (ref "TP139") (pin "P$1") (pinfunction "1_P$1") (pintype "bidirectional"))
      (node (ref "USB1") (pin "1") (pinfunction "1_1") (pintype "input"))
    )
    (net (code "63") (name "Net-(U1-ELE0)") (class "Default")
      (node (ref "TOUCH_A") (pin "P$1") (pinfunction "P$1_P$1") (pintype "bidirectional"))
      (node (ref "U1") (pin "8") (pinfunction "ELE0_8") (pintype "output"))
    )
    (net (code "64") (name "Net-(U1-ELE1)") (class "Default")
      (node (ref "TOUCH_B") (pin "P$1") (pinfunction "P$1_P$1") (pintype "bidirectional"))
      (node (ref "U1") (pin "9") (pinfunction "ELE1_9") (pintype "output"))
    )
    (net (code "65") (name "Net-(U1-ELE2)") (class "Default")
      (node (ref "TOUCH_START") (pin "P$1") (pinfunction "P$1_P$1") (pintype "bidirectional"))
      (node (ref "U1") (pin "10") (pinfunction "ELE2_10") (pintype "output"))
    )
    (net (code "66") (name "Net-(U1-ELE3)") (class "Default")
      (node (ref "TOUCH_SELECT") (pin "P$1") (pinfunction "P$1_P$1") (pintype "bidirectional"))
      (node (ref "U1") (pin "11") (pinfunction "ELE3_11") (pintype "output"))
    )
    (net (code "67") (name "Net-(U1-ELE6)") (class "Default")
      (node (ref "TOUCH_SEL") (pin "UP") (pinfunction "UP_UP") (pintype "bidirectional"))
      (node (ref "U1") (pin "14") (pinfunction "ELE6_14") (pintype "output"))
    )
    (net (code "68") (name "Net-(U1-REXT)") (class "Default")
      (node (ref "R37") (pin "2") (pinfunction "2_2") (pintype "passive"))
      (node (ref "U1") (pin "7") (pinfunction "REXT_7") (pintype "input"))
    )
    (net (code "69") (name "Net-(U1-V_REG)") (class "Default")
      (node (ref "C45") (pin "1") (pinfunction "1_1") (pintype "passive"))
      (node (ref "U1") (pin "5") (pinfunction "V_REG_5") (pintype "input"))
    )
    (net (code "70") (name "PREVGH") (class "Default")
      (node (ref "C32") (pin "2") (pinfunction "2_2") (pintype "passive"))
      (node (ref "D9") (pin "C") (pinfunction "C_C") (pintype "passive"))
      (node (ref "TP104") (pin "P$1") (pinfunction "1_P$1") (pintype "bidirectional"))
      (node (ref "X1") (pin "4") (pinfunction "4_4") (pintype "passive"))
    )
    (net (code "71") (name "PREVGL") (class "Default")
      (node (ref "C36") (pin "2") (pinfunction "2_2") (pintype "passive"))
      (node (ref "D8") (pin "A") (pinfunction "A_A") (pintype "passive"))
      (node (ref "TP105") (pin "P$1") (pinfunction "1_P$1") (pintype "bidirectional"))
      (node (ref "X1") (pin "2") (pinfunction "2_2") (pintype "passive"))
    )
    (net (code "72") (name "RESE") (class "Default")
      (node (ref "Q5") (pin "2") (pinfunction "S_2") (pintype "passive"))
      (node (ref "R19") (pin "1") (pinfunction "1_1") (pintype "passive"))
      (node (ref "TP123") (pin "P$1") (pinfunction "1_P$1") (pintype "bidirectional"))
      (node (ref "X1") (pin "22") (pinfunction "22_22") (pintype "passive"))
    )
    (net (code "73") (name "SD_CD") (class "Default")
      (node (ref "R31") (pin "2") (pinfunction "2_2") (pintype "passive"))
      (node (ref "U1") (pin "19") (pinfunction "ELE11_19") (pintype "output"))
      (node (ref "X2") (pin "CD1") (pinfunction "SHIELD_CD1") (pintype "bidirectional"))
    )
    (net (code "74") (name "SD_CLK") (class "Default")
      (node (ref "IC3") (pin "13") (pinfunction "IO14_13") (pintype "bidirectional"))
      (node (ref "R25") (pin "1") (pinfunction "1_1") (pintype "passive"))
      (node (ref "X2") (pin "5") (pinfunction "SCK_5") (pintype "bidirectional"))
    )
    (net (code "75") (name "SD_CMD") (class "Default")
      (node (ref "IC3") (pin "23") (pinfunction "IO15_23") (pintype "bidirectional"))
      (node (ref "R8") (pin "1") (pinfunction "1_1") (pintype "passive"))
      (node (ref "X2") (pin "3") (pinfunction "DI_3") (pintype "bidirectional"))
    )
    (net (code "76") (name "SD_DATA0") (class "Default")
      (node (ref "D2") (pin "A") (pinfunction "A_A") (pintype "passive"))
      (node (ref "IC3") (pin "24") (pinfunction "IO2_24") (pintype "bidirectional"))
      (node (ref "R5") (pin "1") (pinfunction "1_1") (pintype "passive"))
      (node (ref "X2") (pin "7") (pinfunction "DO_7") (pintype "bidirectional"))
    )
    (net (code "77") (name "SD_DATA3") (class "Default")
      (node (ref "IC3") (pin "16") (pinfunction "IO13_16") (pintype "bidirectional"))
      (node (ref "R17") (pin "1") (pinfunction "1_1") (pintype "passive"))
      (node (ref "X2") (pin "2") (pinfunction "CS_2") (pintype "bidirectional"))
    )
    (net (code "78") (name "TEMP") (class "Default")
      (node (ref "IC4") (pin "1") (pinfunction "TEMP_1") (pintype "bidirectional"))
      (node (ref "R32") (pin "1") (pinfunction "1_1") (pintype "passive"))
      (node (ref "X4") (pin "1") (pinfunction "1_1") (pintype "passive"))
    )
    (net (code "79") (name "TSCL") (class "Default")
      (node (ref "X1") (pin "19") (pinfunction "19_19") (pintype "passive"))
    )
    (net (code "80") (name "TSDA") (class "Default")
      (node (ref "X1") (pin "18") (pinfunction "18_18") (pintype "passive"))
    )
    (net (code "81") (name "USB_DN_CON") (class "Default")
      (node (ref "IC1") (pin "5") (pinfunction "D-_5") (pintype "bidirectional"))
      (node (ref "TP137") (pin "P$1") (pinfunction "1_P$1") (pintype "bidirectional"))
      (node (ref "USB1") (pin "2") (pinfunction "2_2") (pintype "input"))
    )
    (net (code "82") (name "USB_DP_CON") (class "Default")
      (node (ref "IC1") (pin "4") (pinfunction "D+_4") (pintype "bidirectional"))
      (node (ref "TP138") (pin "P$1") (pinfunction "1_P$1") (pintype "bidirectional"))
      (node (ref "USB1") (pin "3") (pinfunction "3_3") (pintype "input"))
    )
    (net (code "83") (name "VBAT") (class "Default")
      (node (ref "F2") (pin "2") (pinfunction "2_2") (pintype "bidirectional"))
      (node (ref "R21") (pin "2") (pinfunction "2_2") (pintype "passive"))
      (node (ref "T1") (pin "3") (pinfunction "D_3") (pintype "passive"))
      (node (ref "TP110") (pin "P$1") (pinfunction "1_P$1") (pintype "bidirectional"))
    )
    (net (code "84") (name "VBAT_SENSE") (class "Default")
      (node (ref "C16") (pin "1") (pinfunction "1_1") (pintype "passive"))
      (node (ref "IC3") (pin "7") (pinfunction "IO35_7") (pintype "bidirectional"))
      (node (ref "R20") (pin "2") (pinfunction "2_2") (pintype "passive"))
      (node (ref "R21") (pin "1") (pinfunction "1_1") (pintype "passive"))
    )
    (net (code "85") (name "VCC") (class "Default")
      (node (ref "C14") (pin "1") (pinfunction "1_1") (pintype "passive"))
      (node (ref "C15") (pin "1") (pinfunction "1_1") (pintype "passive"))
      (node (ref "C18") (pin "1") (pinfunction "1_1") (pintype "passive"))
      (node (ref "D3") (pin "C") (pinfunction "C_C") (pintype "passive"))
      (node (ref "IC2") (pin "3") (pinfunction "IN_3") (pintype "input"))
      (node (ref "R2") (pin "2") (pinfunction "2_2") (pintype "passive"))
      (node (ref "R9") (pin "2") (pinfunction "2_2") (pintype "passive"))
      (node (ref "T1") (pin "2") (pinfunction "S_2") (pintype "passive"))
      (node (ref "T2") (pin "2") (pinfunction "S_2") (pintype "passive"))
      (node (ref "TP129") (pin "P$1") (pinfunction "1_P$1") (pintype "bidirectional"))
    )
    (net (code "86") (name "VCOM") (class "Default")
      (node (ref "C38") (pin "2") (pinfunction "2_2") (pintype "passive"))
      (node (ref "X1") (pin "1") (pinfunction "1_1") (pintype "passive"))
    )
    (net (code "87") (name "VDD") (class "Default")
      (node (ref "C8") (pin "1") (pinfunction "1_1") (pintype "passive"))
      (node (ref "IC1") (pin "6") (pinfunction "VDD_6") (pintype "power_in"))
      (node (ref "R12") (pin "2") (pinfunction "2_2") (pintype "passive"))
      (node (ref "R13") (pin "1") (pinfunction "1_1") (pintype "passive"))
      (node (ref "R14") (pin "2") (pinfunction "2_2") (pintype "passive"))
      (node (ref "R3") (pin "2") (pinfunction "2_2") (pintype "passive"))
    )
    (net (code "88") (name "VGH") (class "Default")
      (node (ref "C21") (pin "2") (pinfunction "2_2") (pintype "passive"))
      (node (ref "X1") (pin "20") (pinfunction "20_20") (pintype "passive"))
    )
    (net (code "89") (name "VGL") (class "Default")
      (node (ref "C19") (pin "2") (pinfunction "2_2") (pintype "passive"))
      (node (ref "X1") (pin "21") (pinfunction "21_21") (pintype "passive"))
    )
    (net (code "90") (name "VIBRATOR") (class "Default")
      (node (ref "R11") (pin "2") (pinfunction "2_2") (pintype "passive"))
      (node (ref "U1") (pin "16") (pinfunction "ELE8_16") (pintype "output"))
    )
    (net (code "91") (name "VPP") (class "Default")
      (node (ref "X1") (pin "6") (pinfunction "6_6") (pintype "passive"))
    )
    (net (code "92") (name "VSH") (class "Default")
      (node (ref "C33") (pin "2") (pinfunction "2_2") (pintype "passive"))
      (node (ref "X1") (pin "5") (pinfunction "5_5") (pintype "passive"))
    )
    (net (code "93") (name "VSL") (class "Default")
      (node (ref "C35") (pin "2") (pinfunction "2_2") (pintype "passive"))
      (node (ref "X1") (pin "3") (pinfunction "3_3") (pintype "passive"))
    )
    (net (code "94") (name "VUSB_SENSE") (class "Default")
      (node (ref "C10") (pin "1") (pinfunction "1_1") (pintype "passive"))
      (node (ref "IC3") (pin "6") (pinfunction "IO34_6") (pintype "bidirectional"))
      (node (ref "R6") (pin "2") (pinfunction "2_2") (pintype "passive"))
      (node (ref "R7") (pin "1") (pinfunction "1_1") (pintype "passive"))
    )
    (net (code "95") (name "WS2812_DATA") (class "Default")
      (node (ref "D105") (pin "4") (pinfunction "DIN_4") (pintype "input"))
      (node (ref "IC3") (pin "8") (pinfunction "IO32_8") (pintype "bidirectional"))
      (node (ref "TP136") (pin "P$1") (pinfunction "1_P$1") (pintype "bidirectional"))
    )
    (net (code "96") (name "WS2812_DATA_OUT") (class "Default")
      (node (ref "D100") (pin "2") (pinfunction "DOUT_2") (pintype "output"))
      (node (ref "X3") (pin "8") (pinfunction "5_8") (pintype "passive"))
    )
    (net (code "97") (name "WS2812_POWER") (class "Default")
      (node (ref "C1") (pin "2") (pinfunction "2_2") (pintype "passive"))
      (node (ref "C13") (pin "1") (pinfunction "1_1") (pintype "passive"))
      (node (ref "C2") (pin "2") (pinfunction "2_2") (pintype "passive"))
      (node (ref "C3") (pin "2") (pinfunction "2_2") (pintype "passive"))
      (node (ref "C4") (pin "2") (pinfunction "2_2") (pintype "passive"))
      (node (ref "C5") (pin "2") (pinfunction "2_2") (pintype "passive"))
      (node (ref "C6") (pin "2") (pinfunction "2_2") (pintype "passive"))
      (node (ref "D100") (pin "1") (pinfunction "VDD_1") (pintype "power_in"))
      (node (ref "D101") (pin "1") (pinfunction "VDD_1") (pintype "power_in"))
      (node (ref "D102") (pin "1") (pinfunction "VDD_1") (pintype "power_in"))
      (node (ref "D103") (pin "1") (pinfunction "VDD_1") (pintype "power_in"))
      (node (ref "D104") (pin "1") (pinfunction "VDD_1") (pintype "power_in"))
      (node (ref "D105") (pin "1") (pinfunction "VDD_1") (pintype "power_in"))
      (node (ref "T2") (pin "3") (pinfunction "D_3") (pintype "passive"))
      (node (ref "TP117") (pin "P$1") (pinfunction "1_P$1") (pintype "bidirectional"))
      (node (ref "X3") (pin "2") (pinfunction "11_2") (pintype "passive"))
    )
    (net (code "98") (name "WS2812_POWER_EN") (class "Default")
      (node (ref "R10") (pin "1") (pinfunction "1_1") (pintype "passive"))
      (node (ref "R27") (pin "1") (pinfunction "1_1") (pintype "passive"))
      (node (ref "U1") (pin "18") (pinfunction "ELE10_18") (pintype "output"))
    )
    (net (code "99") (name "unconnected-(IC1-CTS-Pad23)") (class "Default")
      (node (ref "IC1") (pin "23") (pinfunction "CTS_23") (pintype "input"))
    )
    (net (code "100") (name "unconnected-(IC1-DCD-Pad1)") (class "Default")
      (node (ref "IC1") (pin "1") (pinfunction "DCD_1") (pintype "input"))
    )
    (net (code "101") (name "unconnected-(IC1-DSR-Pad27)") (class "Default")
      (node (ref "IC1") (pin "27") (pinfunction "DSR_27") (pintype "input"))
    )
    (net (code "102") (name "unconnected-(IC1-RI-Pad2)") (class "Default")
      (node (ref "IC1") (pin "2") (pinfunction "RI_2") (pintype "input"))
    )
    (net (code "103") (name "unconnected-(IC1-SUSPEND-Pad12)") (class "Default")
      (node (ref "IC1") (pin "12") (pinfunction "SUSPEND_12") (pintype "output"))
    )
    (net (code "104") (name "unconnected-(IC1-~{SUSPEND}-Pad11)") (class "Default")
      (node (ref "IC1") (pin "11") (pinfunction "~{SUSPEND}_11") (pintype "output"))
    )
    (net (code "105") (name "unconnected-(IC3-IO20-Pad32)") (class "Default")
      (node (ref "IC3") (pin "32") (pinfunction "IO20_32") (pintype "bidirectional"))
    )
    (net (code "106") (name "unconnected-(IC4-STDBY-Pad6)") (class "Default")
      (node (ref "IC4") (pin "6") (pinfunction "STDBY_6") (pintype "bidirectional"))
    )
    (net (code "107") (name "unconnected-(USB1-Pad4)") (class "Default")
      (node (ref "USB1") (pin "4") (pinfunction "4_4") (pintype "input"))
    )
    (net (code "108") (name "unconnected-(X1-Pad24)") (class "Default")
      (node (ref "X1") (pin "24") (pinfunction "24_24") (pintype "passive"))
    )
    (net (code "109") (name "unconnected-(X2-NC-Pad1)") (class "Default")
      (node (ref "X2") (pin "1") (pinfunction "NC_1") (pintype "bidirectional"))
    )
    (net (code "110") (name "unconnected-(X2-RSV-Pad8)") (class "Default")
      (node (ref "X2") (pin "8") (pinfunction "RSV_8") (pintype "bidirectional"))
    )
  )
)
